# 7219_32_16.net
KiCad netlist of a schematic drawn in EAGLE
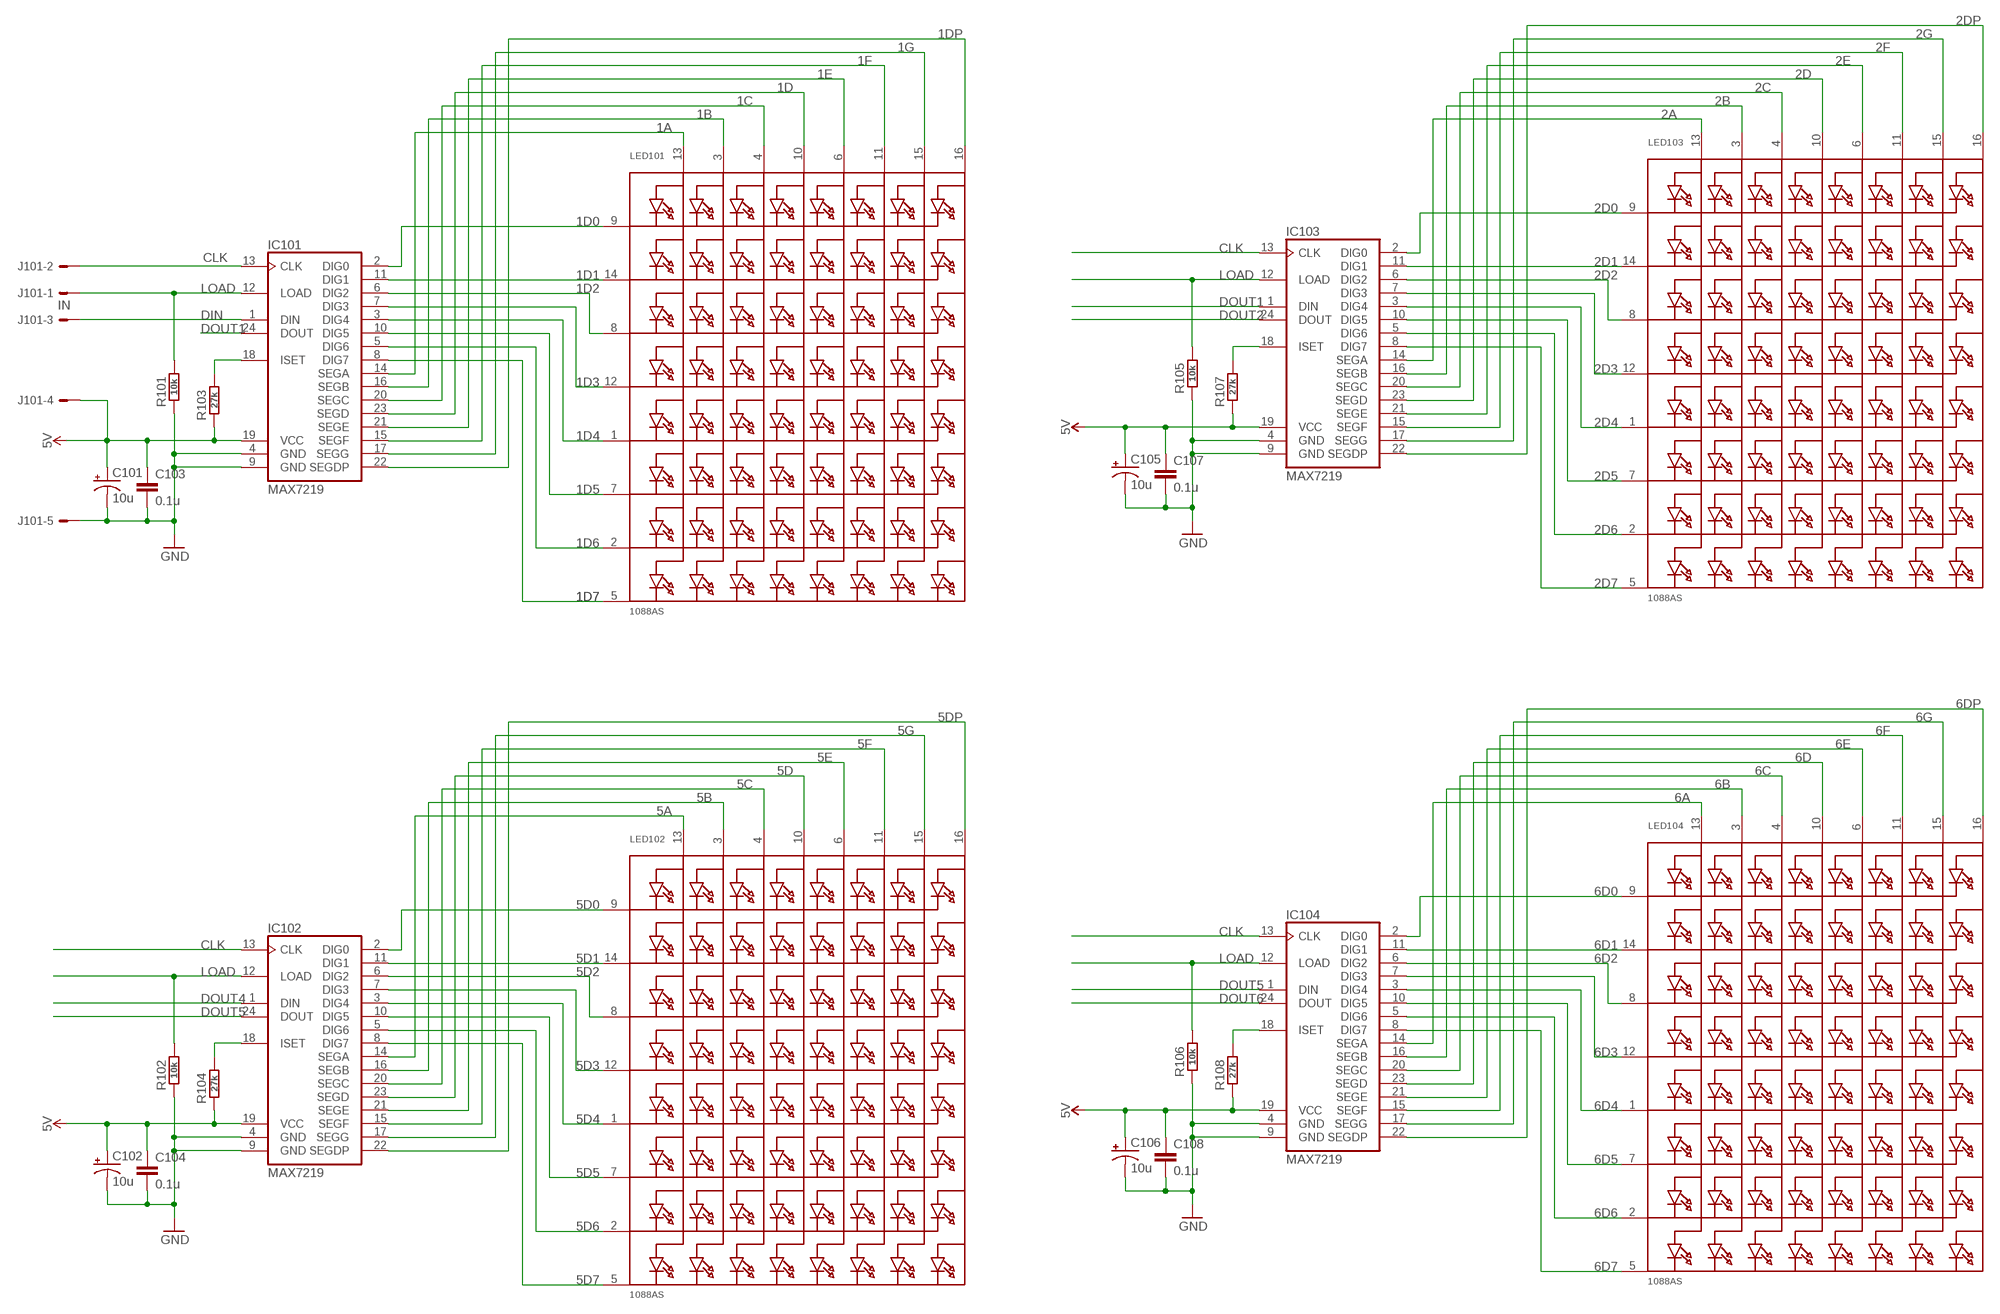
[diagram p0: schematic, sheet 1, part 1 of 2]
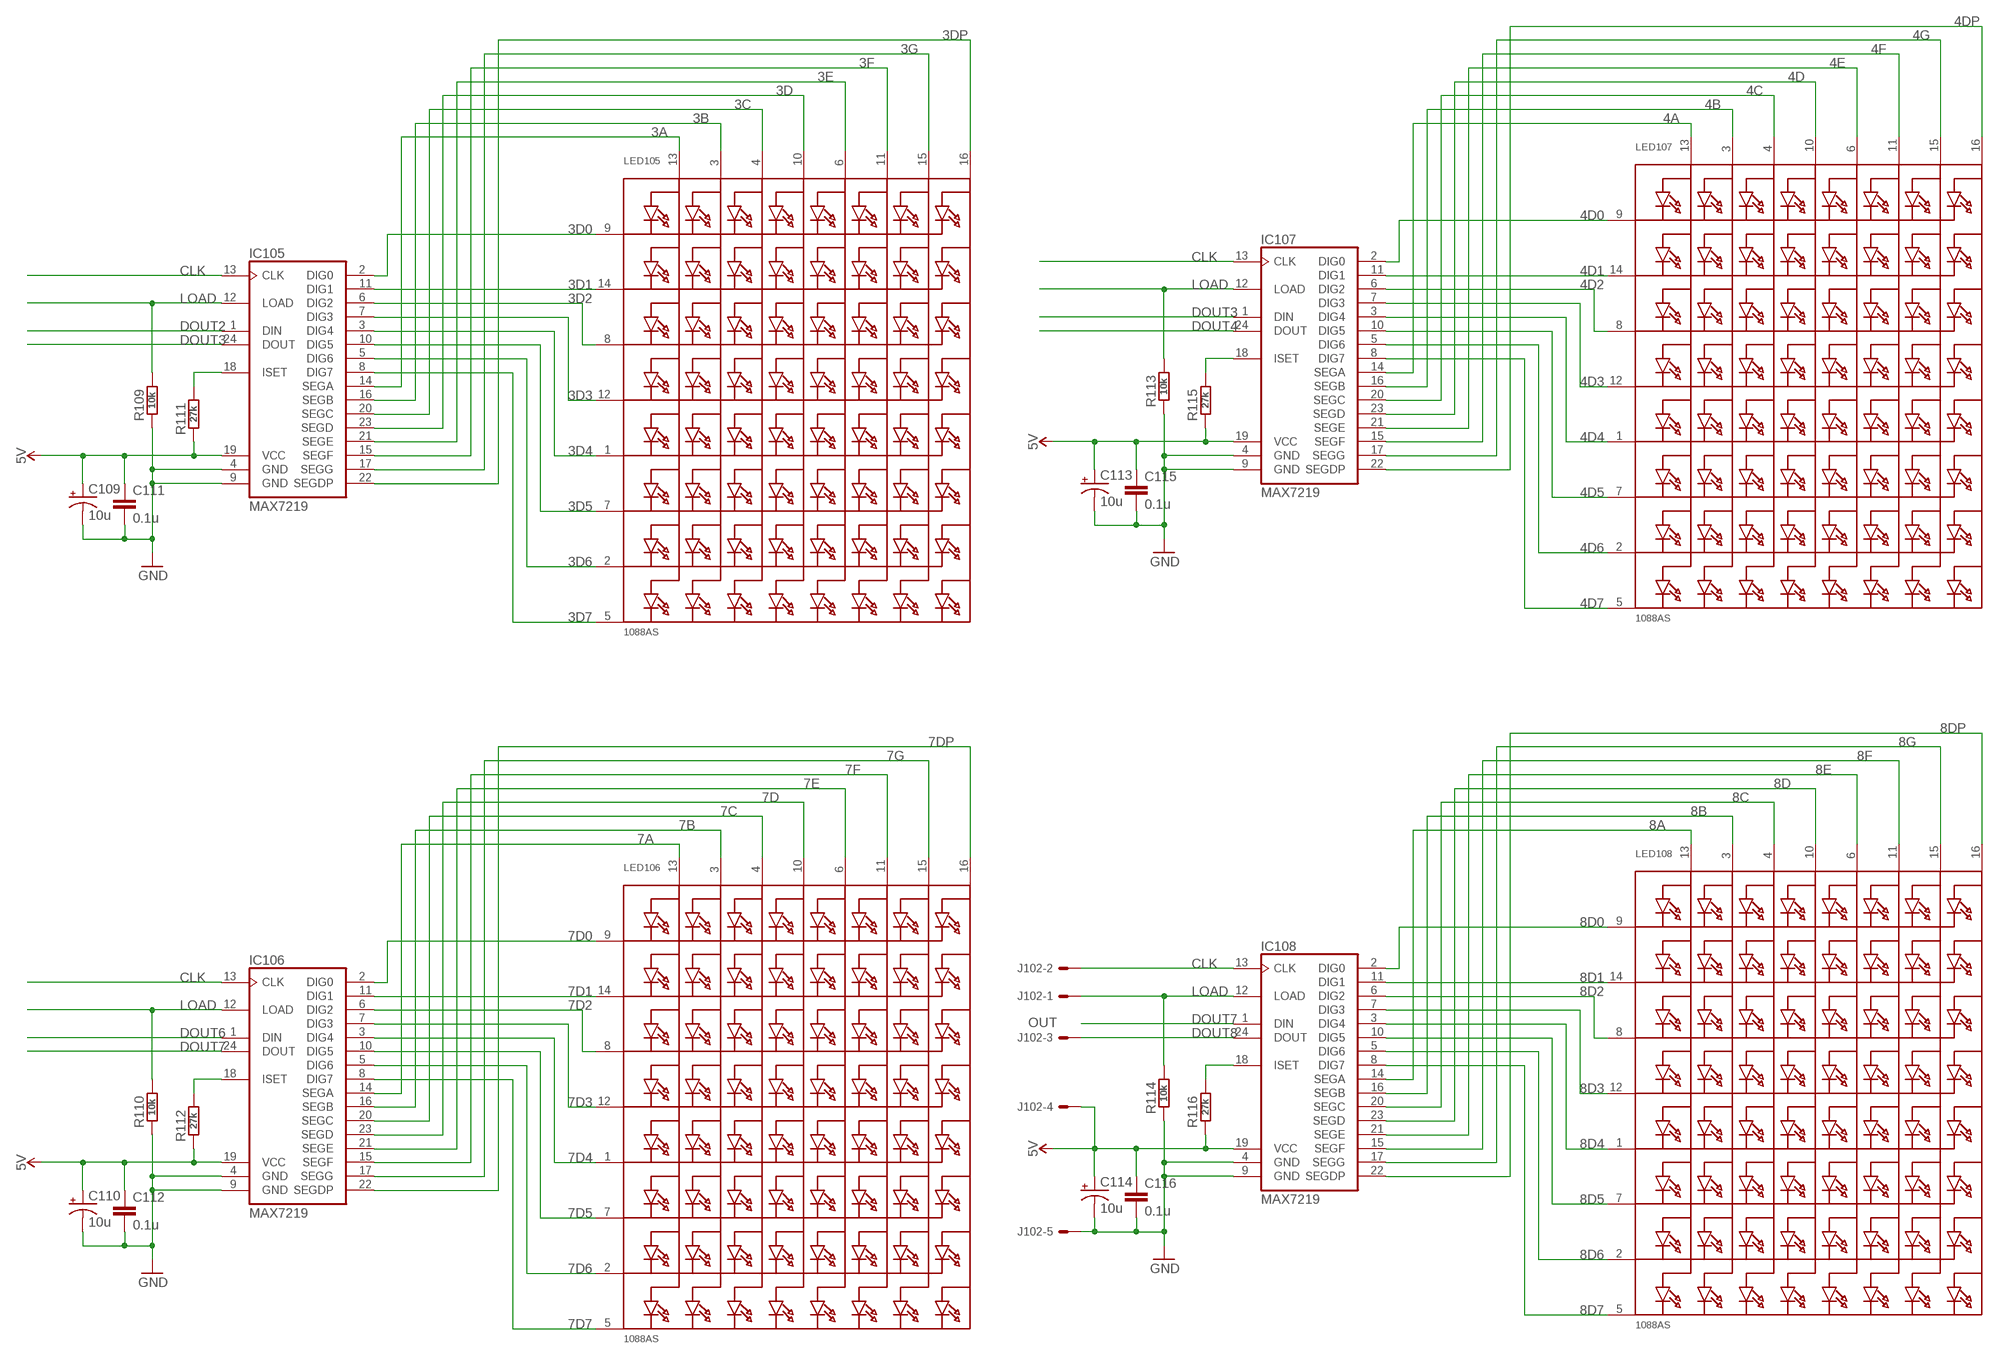
[diagram p1: schematic, sheet 1, part 2 of 2]
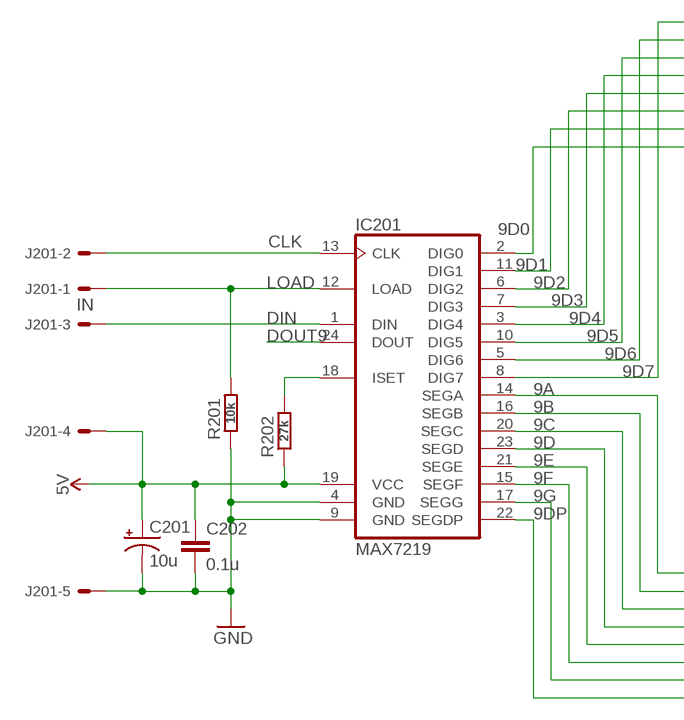
[diagram p2: schematic, sheet 2, part 1 of 2]
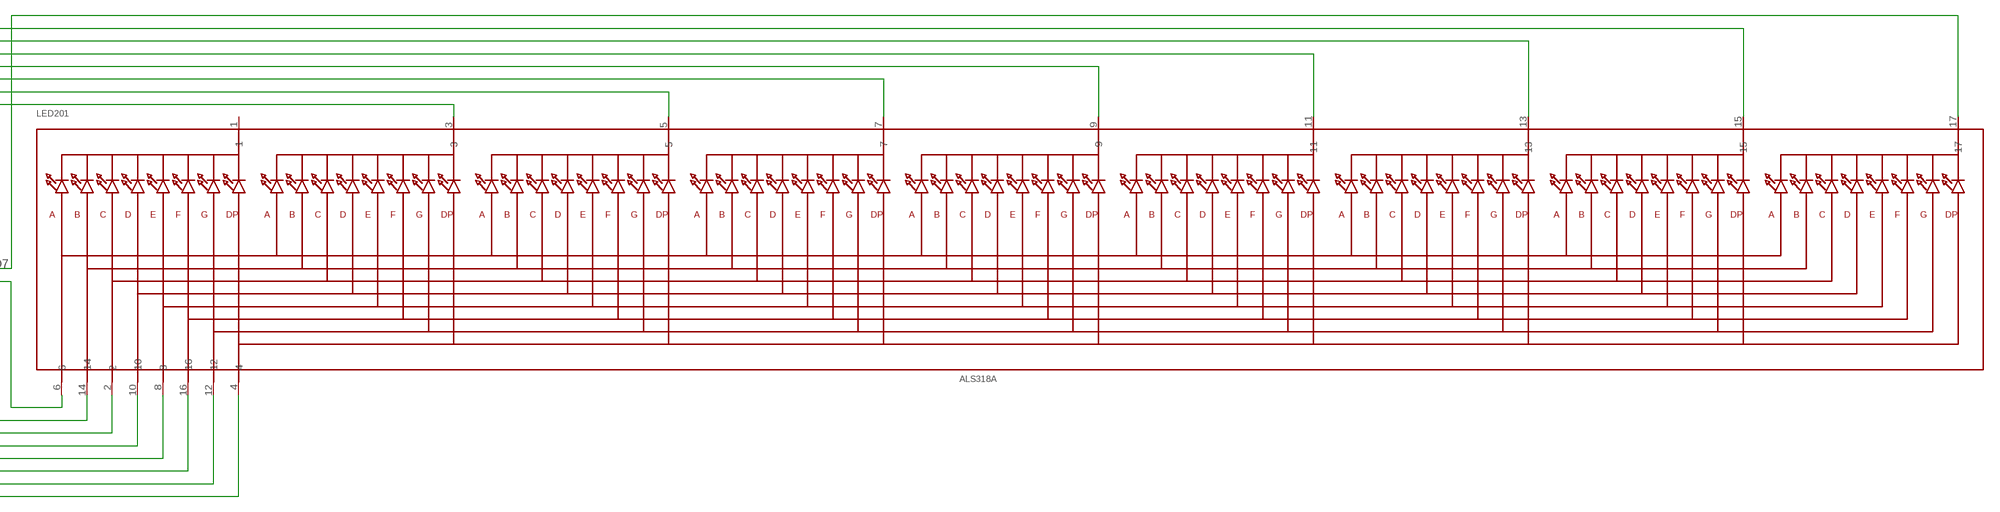
[diagram p3: schematic, sheet 2, part 2 of 2]
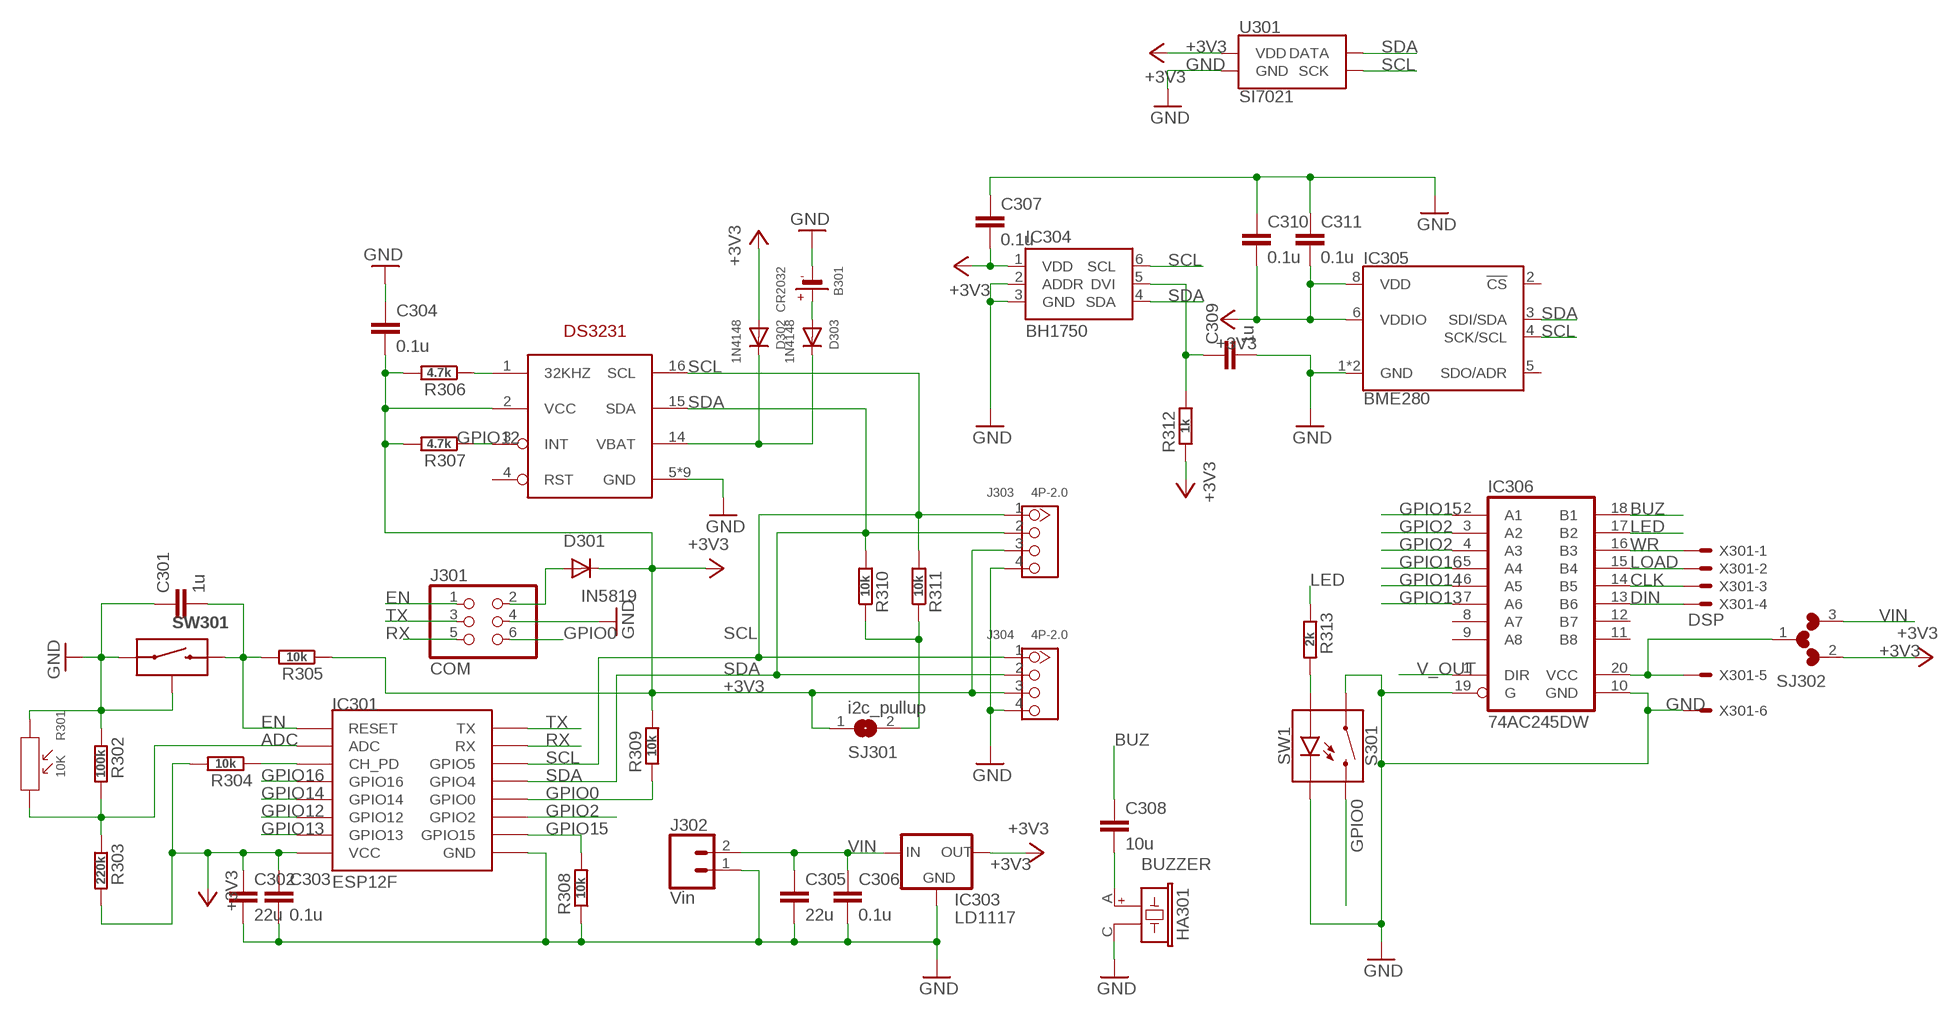
[diagram p4: schematic, sheet 3]
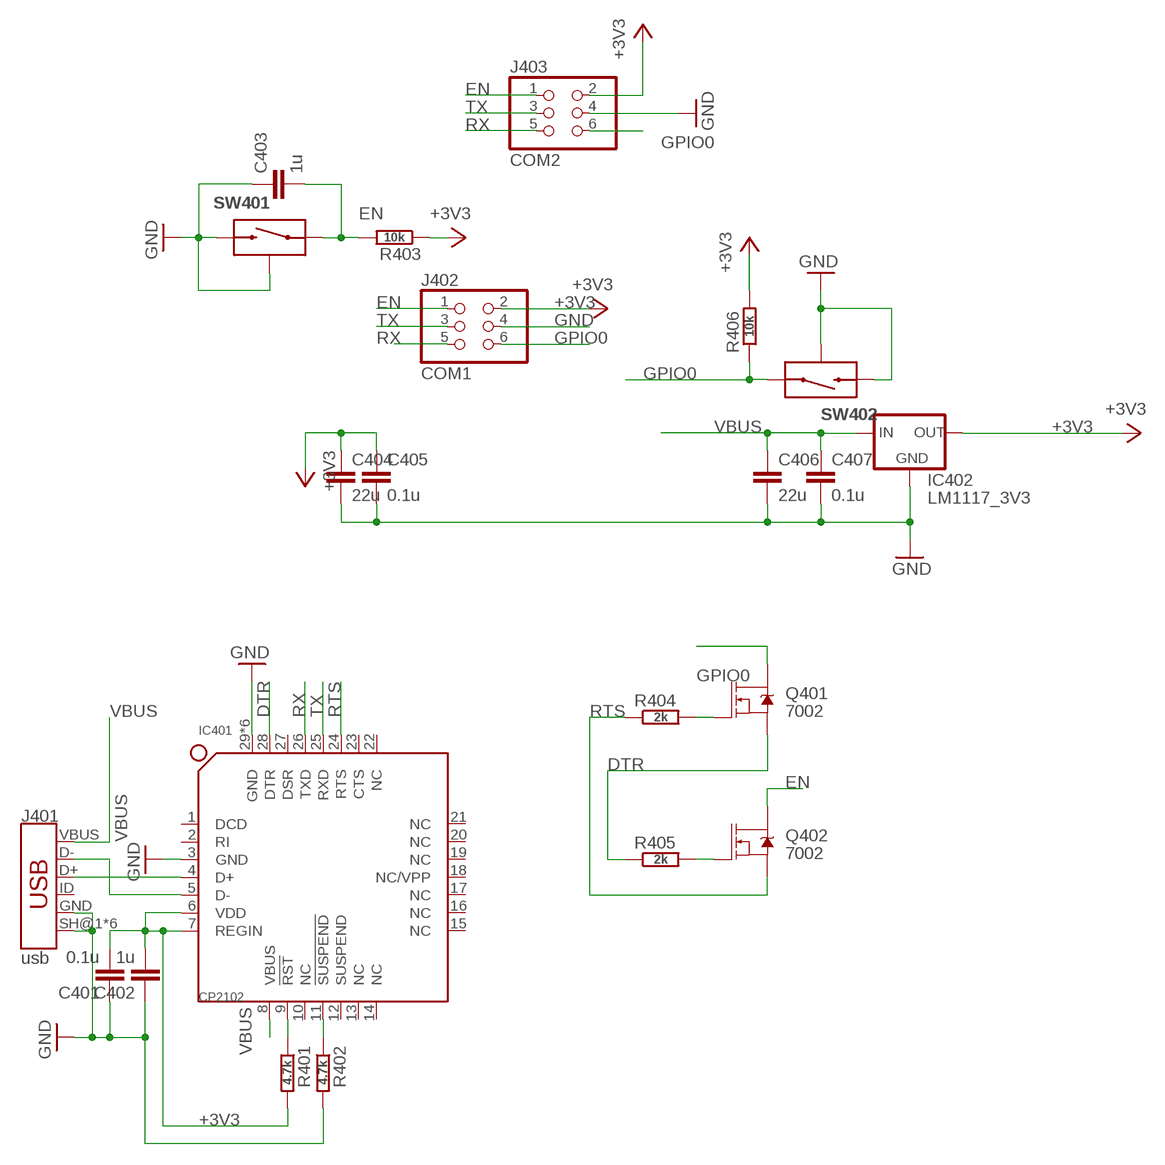
[diagram p5: schematic, sheet 4]

(export (version "E")
  (design (tool "Eeschema 10.0.6"))
  (components
    (comp (ref "B301")
      (value "CR2032")
      (footprint "eagle-import:CR2032")
      (libsource (lib "eagle-import") (part "BATTERYCR2032"))
    )
    (comp (ref "C301")
      (value "1u")
      (footprint "eagle-import:0603-CAP")
      (libsource (lib "eagle-import") (part "CAP0603-CAP"))
    )
    (comp (ref "C302")
      (value "22u")
      (footprint "eagle-import:0603-CAP")
      (libsource (lib "eagle-import") (part "CAP0603-CAP"))
    )
    (comp (ref "C303")
      (value "0.1u")
      (footprint "eagle-import:0603-CAP")
      (libsource (lib "eagle-import") (part "CAP0603-CAP"))
    )
    (comp (ref "C304")
      (value "0.1u")
      (footprint "eagle-import:0603-CAP")
      (libsource (lib "eagle-import") (part "CAP0603-CAP"))
    )
    (comp (ref "C305")
      (value "22u")
      (footprint "eagle-import:0603-CAP")
      (libsource (lib "eagle-import") (part "CAP0603-CAP"))
    )
    (comp (ref "C306")
      (value "0.1u")
      (footprint "eagle-import:0603-CAP")
      (libsource (lib "eagle-import") (part "CAP0603-CAP"))
    )
    (comp (ref "C307")
      (value "0.1u")
      (footprint "eagle-import:0603-CAP")
      (libsource (lib "eagle-import") (part "CAP0603-CAP"))
    )
    (comp (ref "C308")
      (value "10u")
      (footprint "eagle-import:0603-CAP")
      (libsource (lib "eagle-import") (part "CAP0603-CAP"))
    )
    (comp (ref "C309")
      (value "1u")
      (footprint "eagle-import:0603-CAP")
      (libsource (lib "eagle-import") (part "CAP0603-CAP"))
    )
    (comp (ref "C310")
      (value "0.1u")
      (footprint "eagle-import:0603-CAP")
      (libsource (lib "eagle-import") (part "CAP0603-CAP"))
    )
    (comp (ref "C311")
      (value "0.1u")
      (footprint "eagle-import:0603-CAP")
      (libsource (lib "eagle-import") (part "CAP0603-CAP"))
    )
    (comp (ref "D301")
      (value "IN5819")
      (footprint "eagle-import:SOD123")
      (libsource (lib "eagle-import") (part "DIODE-SOD123"))
    )
    (comp (ref "D302")
      (value "1N4148")
      (footprint "eagle-import:SOD-323F")
      (libsource (lib "eagle-import") (part "DIODESOD-323F"))
    )
    (comp (ref "D303")
      (value "1N4148")
      (footprint "eagle-import:SOD-323F")
      (libsource (lib "eagle-import") (part "DIODESOD-323F"))
    )
    (comp (ref "HA301")
      (value "BUZZER")
      (footprint "eagle-import:PBUZ_12X7.5")
      (libsource (lib "eagle-import") (part "PIEZO_BUZZERHYDZ12X7.5"))
    )
    (comp (ref "IC301")
      (value "ESP12F")
      (footprint "eagle-import:ESP12-SMD")
      (libsource (lib "eagle-import") (part "ESP12SMD"))
    )
    (comp (ref "IC302")
      (value "DS3231W")
      (footprint "eagle-import:SO16W")
      (libsource (lib "eagle-import") (part "DS3231W"))
    )
    (comp (ref "IC303")
      (value "LD1117")
      (footprint "eagle-import:SOT223")
      (libsource (lib "eagle-import") (part "V_REG_LD1117VXXSMD"))
    )
    (comp (ref "IC304")
      (value "BH1750")
      (footprint "eagle-import:WSOF6L")
      (libsource (lib "eagle-import") (part "BH1750"))
    )
    (comp (ref "IC305")
      (value "BME280")
      (footprint "eagle-import:LGA-8-2.5X2.5")
      (libsource (lib "eagle-import") (part "BME280"))
    )
    (comp (ref "IC306")
      (value "74AC245DW")
      (footprint "eagle-import:SO20W")
      (libsource (lib "eagle-import") (part "74245DWAC"))
    )
    (comp (ref "J301")
      (value "COM")
      (footprint "eagle-import:2X03_1.27MM_SMT")
      (libsource (lib "eagle-import") (part "HEADER-2X3SMT_1.27"))
    )
    (comp (ref "J302")
      (value "Vin")
      (footprint "eagle-import:1X02")
      (libsource (lib "eagle-import") (part "CONN_02"))
    )
    (comp (ref "J303")
      (value "4P-2.0")
      (footprint "eagle-import:HW4-2.0")
      (libsource (lib "eagle-import") (part "GROVE-CONNECTOR-DIP(4P-2.0)"))
    )
    (comp (ref "J304")
      (value "4P-2.0")
      (footprint "eagle-import:HW4-2.0")
      (libsource (lib "eagle-import") (part "GROVE-CONNECTOR-DIP(4P-2.0)"))
    )
    (comp (ref "R301")
      (value "10K")
      (footprint "eagle-import:SNR2-3.0")
      (fields (field (name "MPN") "PHOTORESISTOR-5528-10K"))
      (libsource (lib "eagle-import") (part "PHOTORESISTOR-5528-10K(2P-5.0X4.2MM)"))
    )
    (comp (ref "R302")
      (value "100k")
      (footprint "eagle-import:R0603")
      (libsource (lib "eagle-import") (part "R-EU_R0603"))
    )
    (comp (ref "R303")
      (value "220k")
      (footprint "eagle-import:R0603")
      (libsource (lib "eagle-import") (part "R-EU_R0603"))
    )
    (comp (ref "R304")
      (value "10k")
      (footprint "eagle-import:R0603")
      (libsource (lib "eagle-import") (part "R-EU_R0603"))
    )
    (comp (ref "R305")
      (value "10k")
      (footprint "eagle-import:R0603")
      (libsource (lib "eagle-import") (part "R-EU_R0603"))
    )
    (comp (ref "R306")
      (value "4.7k")
      (footprint "eagle-import:R0603")
      (libsource (lib "eagle-import") (part "R-EU_R0603"))
    )
    (comp (ref "R307")
      (value "4.7k")
      (footprint "eagle-import:R0603")
      (libsource (lib "eagle-import") (part "R-EU_R0603"))
    )
    (comp (ref "R308")
      (value "10k")
      (footprint "eagle-import:R0603")
      (libsource (lib "eagle-import") (part "R-EU_R0603"))
    )
    (comp (ref "R309")
      (value "10k")
      (footprint "eagle-import:R0603")
      (libsource (lib "eagle-import") (part "R-EU_R0603"))
    )
    (comp (ref "R310")
      (value "10k")
      (footprint "eagle-import:R0603")
      (libsource (lib "eagle-import") (part "R-EU_R0603"))
    )
    (comp (ref "R311")
      (value "10k")
      (footprint "eagle-import:R0603")
      (libsource (lib "eagle-import") (part "R-EU_R0603"))
    )
    (comp (ref "R312")
      (value "1k")
      (footprint "eagle-import:R0603")
      (libsource (lib "eagle-import") (part "R-EU_R0603"))
    )
    (comp (ref "R313")
      (value "2k")
      (footprint "eagle-import:R0603")
      (libsource (lib "eagle-import") (part "R-EU_R0603"))
    )
    (comp (ref "S301")
      (value "SW1")
      (footprint "eagle-import:TACTILE_SWITCH_LED_PTH_12MM_KIT")
      (libsource (lib "eagle-import") (part "MOMENTARY-SWITCH-SPST-LED-PTH-12MM-KIT"))
    )
    (comp (ref "SJ301")
      (value "i2c_pullup")
      (footprint "eagle-import:MICROBUILDER_SOLDERJUMPER_ARROW_NOPASTE")
      (libsource (lib "eagle-import") (part "MICROBUILDER_SOLDERJUMPER"))
    )
    (comp (ref "SJ302")
      (value "MICROBUILDER_SOLDERJUMPER3")
      (footprint "eagle-import:MICROBUILDER_SOLDERJUMPER_ARROW_NOPASTE_3")
      (libsource (lib "eagle-import") (part "MICROBUILDER_SOLDERJUMPER3"))
    )
    (comp (ref "SW301")
      (value "RST")
      (footprint "eagle-import:MICROPUSH-BUT_TOP")
      (libsource (lib "eagle-import") (part "MICROSWITCH-BUTTON"))
    )
    (comp (ref "U301")
      (value "SI7021")
      (footprint "eagle-import:DFN-6-3X3-SI7021")
      (libsource (lib "eagle-import") (part "SI7021"))
    )
    (comp (ref "X301")
      (value "DSP")
      (footprint "eagle-import:70543-06")
      (libsource (lib "eagle-import") (part "C-GRID-06-70543"))
    )
    (comp (ref "C201")
      (value "10u")
      (footprint "eagle-import:EIA3216")
      (libsource (lib "eagle-import") (part "CAP_POL1206"))
    )
    (comp (ref "C202")
      (value "0.1u")
      (footprint "eagle-import:0603-CAP")
      (libsource (lib "eagle-import") (part "CAP0603-CAP"))
    )
    (comp (ref "IC201")
      (value "MAX7219")
      (footprint "eagle-import:SO24L")
      (libsource (lib "eagle-import") (part "MAX7219CNGSO24"))
    )
    (comp (ref "J201")
      (value "IN")
      (footprint "eagle-import:70543-05")
      (libsource (lib "eagle-import") (part "C-GRID-05-70543"))
    )
    (comp (ref "LED201")
      (value "ALS318A")
      (footprint "eagle-import:АЛС318А")
      (libsource (lib "eagle-import") (part "АЛС318АBASE"))
    )
    (comp (ref "R201")
      (value "10k")
      (footprint "eagle-import:R0603")
      (libsource (lib "eagle-import") (part "R-EU_R0603"))
    )
    (comp (ref "R202")
      (value "27k")
      (footprint "eagle-import:R0603")
      (libsource (lib "eagle-import") (part "R-EU_R0603"))
    )
    (comp (ref "C401")
      (value "0.1u")
      (footprint "eagle-import:0603-CAP")
      (libsource (lib "eagle-import") (part "CAP0603-CAP"))
    )
    (comp (ref "C402")
      (value "1u")
      (footprint "eagle-import:0603-CAP")
      (libsource (lib "eagle-import") (part "CAP0603-CAP"))
    )
    (comp (ref "C403")
      (value "1u")
      (footprint "eagle-import:0603-CAP")
      (libsource (lib "eagle-import") (part "CAP0603-CAP"))
    )
    (comp (ref "C404")
      (value "22u")
      (footprint "eagle-import:0603-CAP")
      (libsource (lib "eagle-import") (part "CAP0603-CAP"))
    )
    (comp (ref "C405")
      (value "0.1u")
      (footprint "eagle-import:0603-CAP")
      (libsource (lib "eagle-import") (part "CAP0603-CAP"))
    )
    (comp (ref "C406")
      (value "22u")
      (footprint "eagle-import:0603-CAP")
      (libsource (lib "eagle-import") (part "CAP0603-CAP"))
    )
    (comp (ref "C407")
      (value "0.1u")
      (footprint "eagle-import:0603-CAP")
      (libsource (lib "eagle-import") (part "CAP0603-CAP"))
    )
    (comp (ref "IC401")
      (value "CP2102")
      (footprint "eagle-import:QFN28G_0.5-5X5MM")
      (fields (field (name "MPN") "CP2102-GMR"))
      (libsource (lib "eagle-import") (part "CP2102-GMR(QFN28)"))
    )
    (comp (ref "IC402")
      (value "LM1117_3V3")
      (footprint "eagle-import:SOT223")
      (libsource (lib "eagle-import") (part "V_REG_LD1117VXXSMD"))
    )
    (comp (ref "J401")
      (value "usb")
      (footprint "eagle-import:USB-B-MICRO-SMD_MY")
      (libsource (lib "eagle-import") (part "USB_MICRO-BFEMALE_SMT_"))
    )
    (comp (ref "J402")
      (value "COM1")
      (footprint "eagle-import:2X03_1.27MM_SMT")
      (libsource (lib "eagle-import") (part "HEADER-2X3SMT_1.27"))
    )
    (comp (ref "J403")
      (value "COM2")
      (footprint "eagle-import:2X03")
      (libsource (lib "eagle-import") (part "HEADER-2X3TH"))
    )
    (comp (ref "Q401")
      (value "7002")
      (footprint "eagle-import:SOT23-3")
      (libsource (lib "eagle-import") (part "MOSFET-NCH-2N7002"))
    )
    (comp (ref "Q402")
      (value "7002")
      (footprint "eagle-import:SOT23-3")
      (libsource (lib "eagle-import") (part "MOSFET-NCH-2N7002"))
    )
    (comp (ref "R401")
      (value "4.7k")
      (footprint "eagle-import:R0603")
      (libsource (lib "eagle-import") (part "R-EU_R0603"))
    )
    (comp (ref "R402")
      (value "4.7k")
      (footprint "eagle-import:R0603")
      (libsource (lib "eagle-import") (part "R-EU_R0603"))
    )
    (comp (ref "R403")
      (value "10k")
      (footprint "eagle-import:R0603")
      (libsource (lib "eagle-import") (part "R-EU_R0603"))
    )
    (comp (ref "R404")
      (value "2k")
      (footprint "eagle-import:R0603")
      (libsource (lib "eagle-import") (part "R-EU_R0603"))
    )
    (comp (ref "R405")
      (value "2k")
      (footprint "eagle-import:R0603")
      (libsource (lib "eagle-import") (part "R-EU_R0603"))
    )
    (comp (ref "R406")
      (value "10k")
      (footprint "eagle-import:R0603")
      (libsource (lib "eagle-import") (part "R-EU_R0603"))
    )
    (comp (ref "SW401")
      (value "RST")
      (footprint "eagle-import:MICROPUSH-BUT_TOP")
      (libsource (lib "eagle-import") (part "MICROSWITCH-BUTTON"))
    )
    (comp (ref "SW402")
      (value "PRG")
      (footprint "eagle-import:MICROPUSH-BUT_TOP")
      (libsource (lib "eagle-import") (part "MICROSWITCH-BUTTON"))
    )
    (comp (ref "C101")
      (value "10u")
      (footprint "eagle-import:EIA3216")
      (libsource (lib "eagle-import") (part "CAP_POL1206"))
    )
    (comp (ref "C102")
      (value "10u")
      (footprint "eagle-import:EIA3216")
      (libsource (lib "eagle-import") (part "CAP_POL1206"))
    )
    (comp (ref "C103")
      (value "0.1u")
      (footprint "eagle-import:0603-CAP")
      (libsource (lib "eagle-import") (part "CAP0603-CAP"))
    )
    (comp (ref "C104")
      (value "0.1u")
      (footprint "eagle-import:0603-CAP")
      (libsource (lib "eagle-import") (part "CAP0603-CAP"))
    )
    (comp (ref "C105")
      (value "10u")
      (footprint "eagle-import:EIA3216")
      (libsource (lib "eagle-import") (part "CAP_POL1206"))
    )
    (comp (ref "C106")
      (value "10u")
      (footprint "eagle-import:EIA3216")
      (libsource (lib "eagle-import") (part "CAP_POL1206"))
    )
    (comp (ref "C107")
      (value "0.1u")
      (footprint "eagle-import:0603-CAP")
      (libsource (lib "eagle-import") (part "CAP0603-CAP"))
    )
    (comp (ref "C108")
      (value "0.1u")
      (footprint "eagle-import:0603-CAP")
      (libsource (lib "eagle-import") (part "CAP0603-CAP"))
    )
    (comp (ref "C109")
      (value "10u")
      (footprint "eagle-import:EIA3216")
      (libsource (lib "eagle-import") (part "CAP_POL1206"))
    )
    (comp (ref "C110")
      (value "10u")
      (footprint "eagle-import:EIA3216")
      (libsource (lib "eagle-import") (part "CAP_POL1206"))
    )
    (comp (ref "C111")
      (value "0.1u")
      (footprint "eagle-import:0603-CAP")
      (libsource (lib "eagle-import") (part "CAP0603-CAP"))
    )
    (comp (ref "C112")
      (value "0.1u")
      (footprint "eagle-import:0603-CAP")
      (libsource (lib "eagle-import") (part "CAP0603-CAP"))
    )
    (comp (ref "C113")
      (value "10u")
      (footprint "eagle-import:EIA3216")
      (libsource (lib "eagle-import") (part "CAP_POL1206"))
    )
    (comp (ref "C114")
      (value "10u")
      (footprint "eagle-import:EIA3216")
      (libsource (lib "eagle-import") (part "CAP_POL1206"))
    )
    (comp (ref "C115")
      (value "0.1u")
      (footprint "eagle-import:0603-CAP")
      (libsource (lib "eagle-import") (part "CAP0603-CAP"))
    )
    (comp (ref "C116")
      (value "0.1u")
      (footprint "eagle-import:0603-CAP")
      (libsource (lib "eagle-import") (part "CAP0603-CAP"))
    )
    (comp (ref "IC101")
      (value "MAX7219")
      (footprint "eagle-import:SO24L")
      (libsource (lib "eagle-import") (part "MAX7219CNGSO24"))
    )
    (comp (ref "IC102")
      (value "MAX7219")
      (footprint "eagle-import:SO24L")
      (libsource (lib "eagle-import") (part "MAX7219CNGSO24"))
    )
    (comp (ref "IC103")
      (value "MAX7219")
      (footprint "eagle-import:SO24L")
      (libsource (lib "eagle-import") (part "MAX7219CNGSO24"))
    )
    (comp (ref "IC104")
      (value "MAX7219")
      (footprint "eagle-import:SO24L")
      (libsource (lib "eagle-import") (part "MAX7219CNGSO24"))
    )
    (comp (ref "IC105")
      (value "MAX7219")
      (footprint "eagle-import:SO24L")
      (libsource (lib "eagle-import") (part "MAX7219CNGSO24"))
    )
    (comp (ref "IC106")
      (value "MAX7219")
      (footprint "eagle-import:SO24L")
      (libsource (lib "eagle-import") (part "MAX7219CNGSO24"))
    )
    (comp (ref "IC107")
      (value "MAX7219")
      (footprint "eagle-import:SO24L")
      (libsource (lib "eagle-import") (part "MAX7219CNGSO24"))
    )
    (comp (ref "IC108")
      (value "MAX7219")
      (footprint "eagle-import:SO24L")
      (libsource (lib "eagle-import") (part "MAX7219CNGSO24"))
    )
    (comp (ref "J101")
      (value "IN")
      (footprint "eagle-import:70543-05")
      (libsource (lib "eagle-import") (part "C-GRID-05-70543"))
    )
    (comp (ref "J102")
      (value "OUT")
      (footprint "eagle-import:70543-05")
      (libsource (lib "eagle-import") (part "C-GRID-05-70543"))
    )
    (comp (ref "LED101")
      (value "1088AS")
      (footprint "eagle-import:SEGMENT_BL-M12A881UR")
      (libsource (lib "eagle-import") (part "DISP_SEGMENT_8X8_ROWCATHODEM12A881UR"))
    )
    (comp (ref "LED102")
      (value "1088AS")
      (footprint "eagle-import:SEGMENT_BL-M12A881UR")
      (libsource (lib "eagle-import") (part "DISP_SEGMENT_8X8_ROWCATHODEM12A881UR"))
    )
    (comp (ref "LED103")
      (value "1088AS")
      (footprint "eagle-import:SEGMENT_BL-M12A881UR")
      (libsource (lib "eagle-import") (part "DISP_SEGMENT_8X8_ROWCATHODEM12A881UR"))
    )
    (comp (ref "LED104")
      (value "1088AS")
      (footprint "eagle-import:SEGMENT_BL-M12A881UR")
      (libsource (lib "eagle-import") (part "DISP_SEGMENT_8X8_ROWCATHODEM12A881UR"))
    )
    (comp (ref "LED105")
      (value "1088AS")
      (footprint "eagle-import:SEGMENT_BL-M12A881UR")
      (libsource (lib "eagle-import") (part "DISP_SEGMENT_8X8_ROWCATHODEM12A881UR"))
    )
    (comp (ref "LED106")
      (value "1088AS")
      (footprint "eagle-import:SEGMENT_BL-M12A881UR")
      (libsource (lib "eagle-import") (part "DISP_SEGMENT_8X8_ROWCATHODEM12A881UR"))
    )
    (comp (ref "LED107")
      (value "1088AS")
      (footprint "eagle-import:SEGMENT_BL-M12A881UR")
      (libsource (lib "eagle-import") (part "DISP_SEGMENT_8X8_ROWCATHODEM12A881UR"))
    )
    (comp (ref "LED108")
      (value "1088AS")
      (footprint "eagle-import:SEGMENT_BL-M12A881UR")
      (libsource (lib "eagle-import") (part "DISP_SEGMENT_8X8_ROWCATHODEM12A881UR"))
    )
    (comp (ref "R101")
      (value "10k")
      (footprint "eagle-import:R0603")
      (libsource (lib "eagle-import") (part "R-EU_R0603"))
    )
    (comp (ref "R102")
      (value "10k")
      (footprint "eagle-import:R0603")
      (libsource (lib "eagle-import") (part "R-EU_R0603"))
    )
    (comp (ref "R103")
      (value "27k")
      (footprint "eagle-import:R0603")
      (libsource (lib "eagle-import") (part "R-EU_R0603"))
    )
    (comp (ref "R104")
      (value "27k")
      (footprint "eagle-import:R0603")
      (libsource (lib "eagle-import") (part "R-EU_R0603"))
    )
    (comp (ref "R105")
      (value "10k")
      (footprint "eagle-import:R0603")
      (libsource (lib "eagle-import") (part "R-EU_R0603"))
    )
    (comp (ref "R106")
      (value "10k")
      (footprint "eagle-import:R0603")
      (libsource (lib "eagle-import") (part "R-EU_R0603"))
    )
    (comp (ref "R107")
      (value "27k")
      (footprint "eagle-import:R0603")
      (libsource (lib "eagle-import") (part "R-EU_R0603"))
    )
    (comp (ref "R108")
      (value "27k")
      (footprint "eagle-import:R0603")
      (libsource (lib "eagle-import") (part "R-EU_R0603"))
    )
    (comp (ref "R109")
      (value "10k")
      (footprint "eagle-import:R0603")
      (libsource (lib "eagle-import") (part "R-EU_R0603"))
    )
    (comp (ref "R110")
      (value "10k")
      (footprint "eagle-import:R0603")
      (libsource (lib "eagle-import") (part "R-EU_R0603"))
    )
    (comp (ref "R111")
      (value "27k")
      (footprint "eagle-import:R0603")
      (libsource (lib "eagle-import") (part "R-EU_R0603"))
    )
    (comp (ref "R112")
      (value "27k")
      (footprint "eagle-import:R0603")
      (libsource (lib "eagle-import") (part "R-EU_R0603"))
    )
    (comp (ref "R113")
      (value "10k")
      (footprint "eagle-import:R0603")
      (libsource (lib "eagle-import") (part "R-EU_R0603"))
    )
    (comp (ref "R114")
      (value "10k")
      (footprint "eagle-import:R0603")
      (libsource (lib "eagle-import") (part "R-EU_R0603"))
    )
    (comp (ref "R115")
      (value "27k")
      (footprint "eagle-import:R0603")
      (libsource (lib "eagle-import") (part "R-EU_R0603"))
    )
    (comp (ref "R116")
      (value "27k")
      (footprint "eagle-import:R0603")
      (libsource (lib "eagle-import") (part "R-EU_R0603"))
    )
  )
  (nets
    (net (code "1") (name "+3V3") (class "Default")
      (node (ref "C302") (pin "1") (pinfunction "1_1") (pintype "passive"))
      (node (ref "C303") (pin "1") (pinfunction "1_1") (pintype "passive"))
      (node (ref "C304") (pin "2") (pinfunction "2_2") (pintype "passive"))
      (node (ref "C307") (pin "2") (pinfunction "2_2") (pintype "passive"))
      (node (ref "C310") (pin "2") (pinfunction "2_2") (pintype "passive"))
      (node (ref "C311") (pin "2") (pinfunction "2_2") (pintype "passive"))
      (node (ref "C401") (pin "2") (pinfunction "2_2") (pintype "passive"))
      (node (ref "C402") (pin "2") (pinfunction "2_2") (pintype "passive"))
      (node (ref "C404") (pin "1") (pinfunction "1_1") (pintype "passive"))
      (node (ref "C405") (pin "1") (pinfunction "1_1") (pintype "passive"))
      (node (ref "D301") (pin "C") (pinfunction "C_C") (pintype "passive"))
      (node (ref "D302") (pin "A") (pinfunction "A_A") (pintype "passive"))
      (node (ref "IC301") (pin "VCC") (pinfunction "VCC_VCC") (pintype "bidirectional"))
      (node (ref "IC302") (pin "2") (pinfunction "VCC_2") (pintype "input"))
      (node (ref "IC303") (pin "2") (pinfunction "OUT_2") (pintype "passive"))
      (node (ref "IC303") (pin "4") (pinfunction "OUT_4") (pintype "passive"))
      (node (ref "IC304") (pin "1") (pinfunction "VDD_1") (pintype "power_in"))
      (node (ref "IC305") (pin "6") (pinfunction "VDDIO_6") (pintype "bidirectional"))
      (node (ref "IC305") (pin "8") (pinfunction "VDD_8") (pintype "bidirectional"))
      (node (ref "IC401") (pin "6") (pinfunction "VDD_6") (pintype "bidirectional"))
      (node (ref "IC401") (pin "7") (pinfunction "REGIN_7") (pintype "bidirectional"))
      (node (ref "IC402") (pin "2") (pinfunction "OUT_2") (pintype "passive"))
      (node (ref "IC402") (pin "4") (pinfunction "OUT_4") (pintype "passive"))
      (node (ref "J303") (pin "3") (pinfunction "3_3") (pintype "bidirectional"))
      (node (ref "J304") (pin "3") (pinfunction "3_3") (pintype "bidirectional"))
      (node (ref "J402") (pin "2") (pinfunction "2_2") (pintype "passive"))
      (node (ref "J403") (pin "2") (pinfunction "2_2") (pintype "passive"))
      (node (ref "R303") (pin "2") (pinfunction "2_2") (pintype "passive"))
      (node (ref "R304") (pin "2") (pinfunction "2_2") (pintype "passive"))
      (node (ref "R305") (pin "1") (pinfunction "1_1") (pintype "passive"))
      (node (ref "R306") (pin "2") (pinfunction "2_2") (pintype "passive"))
      (node (ref "R307") (pin "2") (pinfunction "2_2") (pintype "passive"))
      (node (ref "R309") (pin "2") (pinfunction "2_2") (pintype "passive"))
      (node (ref "R312") (pin "1") (pinfunction "1_1") (pintype "passive"))
      (node (ref "R401") (pin "2") (pinfunction "2_2") (pintype "passive"))
      (node (ref "R403") (pin "1") (pinfunction "1_1") (pintype "passive"))
      (node (ref "R406") (pin "2") (pinfunction "2_2") (pintype "passive"))
      (node (ref "SJ301") (pin "1") (pinfunction "1_1") (pintype "passive"))
      (node (ref "SJ302") (pin "2") (pinfunction "2_2") (pintype "passive"))
      (node (ref "U301") (pin "VDD") (pinfunction "VDD_VDD") (pintype "power_in"))
    )
    (net (code "2") (name "+5V") (class "Default")
      (node (ref "C101") (pin "A") (pinfunction "+_A") (pintype "passive"))
      (node (ref "C102") (pin "A") (pinfunction "+_A") (pintype "passive"))
      (node (ref "C103") (pin "1") (pinfunction "1_1") (pintype "passive"))
      (node (ref "C104") (pin "1") (pinfunction "1_1") (pintype "passive"))
      (node (ref "C105") (pin "A") (pinfunction "+_A") (pintype "passive"))
      (node (ref "C106") (pin "A") (pinfunction "+_A") (pintype "passive"))
      (node (ref "C107") (pin "1") (pinfunction "1_1") (pintype "passive"))
      (node (ref "C108") (pin "1") (pinfunction "1_1") (pintype "passive"))
      (node (ref "C109") (pin "A") (pinfunction "+_A") (pintype "passive"))
      (node (ref "C110") (pin "A") (pinfunction "+_A") (pintype "passive"))
      (node (ref "C111") (pin "1") (pinfunction "1_1") (pintype "passive"))
      (node (ref "C112") (pin "1") (pinfunction "1_1") (pintype "passive"))
      (node (ref "C113") (pin "A") (pinfunction "+_A") (pintype "passive"))
      (node (ref "C114") (pin "A") (pinfunction "+_A") (pintype "passive"))
      (node (ref "C115") (pin "1") (pinfunction "1_1") (pintype "passive"))
      (node (ref "C116") (pin "1") (pinfunction "1_1") (pintype "passive"))
      (node (ref "C201") (pin "A") (pinfunction "+_A") (pintype "passive"))
      (node (ref "C202") (pin "1") (pinfunction "1_1") (pintype "passive"))
      (node (ref "IC101") (pin "19") (pinfunction "VCC_19") (pintype "power_in"))
      (node (ref "IC102") (pin "19") (pinfunction "VCC_19") (pintype "power_in"))
      (node (ref "IC103") (pin "19") (pinfunction "VCC_19") (pintype "power_in"))
      (node (ref "IC104") (pin "19") (pinfunction "VCC_19") (pintype "power_in"))
      (node (ref "IC105") (pin "19") (pinfunction "VCC_19") (pintype "power_in"))
      (node (ref "IC106") (pin "19") (pinfunction "VCC_19") (pintype "power_in"))
      (node (ref "IC107") (pin "19") (pinfunction "VCC_19") (pintype "power_in"))
      (node (ref "IC108") (pin "19") (pinfunction "VCC_19") (pintype "power_in"))
      (node (ref "IC201") (pin "19") (pinfunction "VCC_19") (pintype "power_in"))
      (node (ref "J101") (pin "4") (pinfunction "S_4") (pintype "passive"))
      (node (ref "J102") (pin "4") (pinfunction "S_4") (pintype "passive"))
      (node (ref "J201") (pin "4") (pinfunction "S_4") (pintype "passive"))
      (node (ref "R103") (pin "1") (pinfunction "1_1") (pintype "passive"))
      (node (ref "R104") (pin "1") (pinfunction "1_1") (pintype "passive"))
      (node (ref "R107") (pin "1") (pinfunction "1_1") (pintype "passive"))
      (node (ref "R108") (pin "1") (pinfunction "1_1") (pintype "passive"))
      (node (ref "R111") (pin "1") (pinfunction "1_1") (pintype "passive"))
      (node (ref "R112") (pin "1") (pinfunction "1_1") (pintype "passive"))
      (node (ref "R115") (pin "1") (pinfunction "1_1") (pintype "passive"))
      (node (ref "R116") (pin "1") (pinfunction "1_1") (pintype "passive"))
      (node (ref "R202") (pin "1") (pinfunction "1_1") (pintype "passive"))
    )
    (net (code "3") (name "1A") (class "Default")
      (node (ref "IC101") (pin "14") (pinfunction "SEGA_14") (pintype "output"))
      (node (ref "LED101") (pin "13") (pinfunction "A1_13") (pintype "bidirectional"))
    )
    (net (code "4") (name "1B") (class "Default")
      (node (ref "IC101") (pin "16") (pinfunction "SEGB_16") (pintype "output"))
      (node (ref "LED101") (pin "3") (pinfunction "A2_3") (pintype "bidirectional"))
    )
    (net (code "5") (name "1C") (class "Default")
      (node (ref "IC101") (pin "20") (pinfunction "SEGC_20") (pintype "output"))
      (node (ref "LED101") (pin "4") (pinfunction "A3_4") (pintype "bidirectional"))
    )
    (net (code "6") (name "1D") (class "Default")
      (node (ref "IC101") (pin "23") (pinfunction "SEGD_23") (pintype "output"))
      (node (ref "LED101") (pin "10") (pinfunction "A4_10") (pintype "bidirectional"))
    )
    (net (code "7") (name "1D0") (class "Default")
      (node (ref "IC101") (pin "2") (pinfunction "DIG0_2") (pintype "output"))
      (node (ref "LED101") (pin "9") (pinfunction "K1_9") (pintype "bidirectional"))
    )
    (net (code "8") (name "1D1") (class "Default")
      (node (ref "IC101") (pin "11") (pinfunction "DIG1_11") (pintype "output"))
      (node (ref "LED101") (pin "14") (pinfunction "K2_14") (pintype "bidirectional"))
    )
    (net (code "9") (name "1D2") (class "Default")
      (node (ref "IC101") (pin "6") (pinfunction "DIG2_6") (pintype "output"))
      (node (ref "LED101") (pin "8") (pinfunction "K3_8") (pintype "bidirectional"))
    )
    (net (code "10") (name "1D3") (class "Default")
      (node (ref "IC101") (pin "7") (pinfunction "DIG3_7") (pintype "output"))
      (node (ref "LED101") (pin "12") (pinfunction "K4_12") (pintype "bidirectional"))
    )
    (net (code "11") (name "1D4") (class "Default")
      (node (ref "IC101") (pin "3") (pinfunction "DIG4_3") (pintype "output"))
      (node (ref "LED101") (pin "1") (pinfunction "K5_1") (pintype "bidirectional"))
    )
    (net (code "12") (name "1D5") (class "Default")
      (node (ref "IC101") (pin "10") (pinfunction "DIG5_10") (pintype "output"))
      (node (ref "LED101") (pin "7") (pinfunction "K6_7") (pintype "bidirectional"))
    )
    (net (code "13") (name "1D6") (class "Default")
      (node (ref "IC101") (pin "5") (pinfunction "DIG6_5") (pintype "output"))
      (node (ref "LED101") (pin "2") (pinfunction "K7_2") (pintype "bidirectional"))
    )
    (net (code "14") (name "1D7") (class "Default")
      (node (ref "IC101") (pin "8") (pinfunction "DIG7_8") (pintype "output"))
      (node (ref "LED101") (pin "5") (pinfunction "K8_5") (pintype "bidirectional"))
    )
    (net (code "15") (name "1DP") (class "Default")
      (node (ref "IC101") (pin "22") (pinfunction "SEGDP_22") (pintype "output"))
      (node (ref "LED101") (pin "16") (pinfunction "A8_16") (pintype "bidirectional"))
    )
    (net (code "16") (name "1E") (class "Default")
      (node (ref "IC101") (pin "21") (pinfunction "SEGE_21") (pintype "output"))
      (node (ref "LED101") (pin "6") (pinfunction "A5_6") (pintype "bidirectional"))
    )
    (net (code "17") (name "1F") (class "Default")
      (node (ref "IC101") (pin "15") (pinfunction "SEGF_15") (pintype "output"))
      (node (ref "LED101") (pin "11") (pinfunction "A6_11") (pintype "bidirectional"))
    )
    (net (code "18") (name "1G") (class "Default")
      (node (ref "IC101") (pin "17") (pinfunction "SEGG_17") (pintype "output"))
      (node (ref "LED101") (pin "15") (pinfunction "A7_15") (pintype "bidirectional"))
    )
    (net (code "19") (name "2A") (class "Default")
      (node (ref "IC103") (pin "14") (pinfunction "SEGA_14") (pintype "output"))
      (node (ref "LED103") (pin "13") (pinfunction "A1_13") (pintype "bidirectional"))
    )
    (net (code "20") (name "2B") (class "Default")
      (node (ref "IC103") (pin "16") (pinfunction "SEGB_16") (pintype "output"))
      (node (ref "LED103") (pin "3") (pinfunction "A2_3") (pintype "bidirectional"))
    )
    (net (code "21") (name "2C") (class "Default")
      (node (ref "IC103") (pin "20") (pinfunction "SEGC_20") (pintype "output"))
      (node (ref "LED103") (pin "4") (pinfunction "A3_4") (pintype "bidirectional"))
    )
    (net (code "22") (name "2D") (class "Default")
      (node (ref "IC103") (pin "23") (pinfunction "SEGD_23") (pintype "output"))
      (node (ref "LED103") (pin "10") (pinfunction "A4_10") (pintype "bidirectional"))
    )
    (net (code "23") (name "2D0") (class "Default")
      (node (ref "IC103") (pin "2") (pinfunction "DIG0_2") (pintype "output"))
      (node (ref "LED103") (pin "9") (pinfunction "K1_9") (pintype "bidirectional"))
    )
    (net (code "24") (name "2D1") (class "Default")
      (node (ref "IC103") (pin "11") (pinfunction "DIG1_11") (pintype "output"))
      (node (ref "LED103") (pin "14") (pinfunction "K2_14") (pintype "bidirectional"))
    )
    (net (code "25") (name "2D2") (class "Default")
      (node (ref "IC103") (pin "6") (pinfunction "DIG2_6") (pintype "output"))
      (node (ref "LED103") (pin "8") (pinfunction "K3_8") (pintype "bidirectional"))
    )
    (net (code "26") (name "2D3") (class "Default")
      (node (ref "IC103") (pin "7") (pinfunction "DIG3_7") (pintype "output"))
      (node (ref "LED103") (pin "12") (pinfunction "K4_12") (pintype "bidirectional"))
    )
    (net (code "27") (name "2D4") (class "Default")
      (node (ref "IC103") (pin "3") (pinfunction "DIG4_3") (pintype "output"))
      (node (ref "LED103") (pin "1") (pinfunction "K5_1") (pintype "bidirectional"))
    )
    (net (code "28") (name "2D5") (class "Default")
      (node (ref "IC103") (pin "10") (pinfunction "DIG5_10") (pintype "output"))
      (node (ref "LED103") (pin "7") (pinfunction "K6_7") (pintype "bidirectional"))
    )
    (net (code "29") (name "2D6") (class "Default")
      (node (ref "IC103") (pin "5") (pinfunction "DIG6_5") (pintype "output"))
      (node (ref "LED103") (pin "2") (pinfunction "K7_2") (pintype "bidirectional"))
    )
    (net (code "30") (name "2D7") (class "Default")
      (node (ref "IC103") (pin "8") (pinfunction "DIG7_8") (pintype "output"))
      (node (ref "LED103") (pin "5") (pinfunction "K8_5") (pintype "bidirectional"))
    )
    (net (code "31") (name "2DP") (class "Default")
      (node (ref "IC103") (pin "22") (pinfunction "SEGDP_22") (pintype "output"))
      (node (ref "LED103") (pin "16") (pinfunction "A8_16") (pintype "bidirectional"))
    )
    (net (code "32") (name "2E") (class "Default")
      (node (ref "IC103") (pin "21") (pinfunction "SEGE_21") (pintype "output"))
      (node (ref "LED103") (pin "6") (pinfunction "A5_6") (pintype "bidirectional"))
    )
    (net (code "33") (name "2F") (class "Default")
      (node (ref "IC103") (pin "15") (pinfunction "SEGF_15") (pintype "output"))
      (node (ref "LED103") (pin "11") (pinfunction "A6_11") (pintype "bidirectional"))
    )
    (net (code "34") (name "2G") (class "Default")
      (node (ref "IC103") (pin "17") (pinfunction "SEGG_17") (pintype "output"))
      (node (ref "LED103") (pin "15") (pinfunction "A7_15") (pintype "bidirectional"))
    )
    (net (code "35") (name "3A") (class "Default")
      (node (ref "IC105") (pin "14") (pinfunction "SEGA_14") (pintype "output"))
      (node (ref "LED105") (pin "13") (pinfunction "A1_13") (pintype "bidirectional"))
    )
    (net (code "36") (name "3B") (class "Default")
      (node (ref "IC105") (pin "16") (pinfunction "SEGB_16") (pintype "output"))
      (node (ref "LED105") (pin "3") (pinfunction "A2_3") (pintype "bidirectional"))
    )
    (net (code "37") (name "3C") (class "Default")
      (node (ref "IC105") (pin "20") (pinfunction "SEGC_20") (pintype "output"))
      (node (ref "LED105") (pin "4") (pinfunction "A3_4") (pintype "bidirectional"))
    )
    (net (code "38") (name "3D") (class "Default")
      (node (ref "IC105") (pin "23") (pinfunction "SEGD_23") (pintype "output"))
      (node (ref "LED105") (pin "10") (pinfunction "A4_10") (pintype "bidirectional"))
    )
    (net (code "39") (name "3D0") (class "Default")
      (node (ref "IC105") (pin "2") (pinfunction "DIG0_2") (pintype "output"))
      (node (ref "LED105") (pin "9") (pinfunction "K1_9") (pintype "bidirectional"))
    )
    (net (code "40") (name "3D1") (class "Default")
      (node (ref "IC105") (pin "11") (pinfunction "DIG1_11") (pintype "output"))
      (node (ref "LED105") (pin "14") (pinfunction "K2_14") (pintype "bidirectional"))
    )
    (net (code "41") (name "3D2") (class "Default")
      (node (ref "IC105") (pin "6") (pinfunction "DIG2_6") (pintype "output"))
      (node (ref "LED105") (pin "8") (pinfunction "K3_8") (pintype "bidirectional"))
    )
    (net (code "42") (name "3D3") (class "Default")
      (node (ref "IC105") (pin "7") (pinfunction "DIG3_7") (pintype "output"))
      (node (ref "LED105") (pin "12") (pinfunction "K4_12") (pintype "bidirectional"))
    )
    (net (code "43") (name "3D4") (class "Default")
      (node (ref "IC105") (pin "3") (pinfunction "DIG4_3") (pintype "output"))
      (node (ref "LED105") (pin "1") (pinfunction "K5_1") (pintype "bidirectional"))
    )
    (net (code "44") (name "3D5") (class "Default")
      (node (ref "IC105") (pin "10") (pinfunction "DIG5_10") (pintype "output"))
      (node (ref "LED105") (pin "7") (pinfunction "K6_7") (pintype "bidirectional"))
    )
    (net (code "45") (name "3D6") (class "Default")
      (node (ref "IC105") (pin "5") (pinfunction "DIG6_5") (pintype "output"))
      (node (ref "LED105") (pin "2") (pinfunction "K7_2") (pintype "bidirectional"))
    )
    (net (code "46") (name "3D7") (class "Default")
      (node (ref "IC105") (pin "8") (pinfunction "DIG7_8") (pintype "output"))
      (node (ref "LED105") (pin "5") (pinfunction "K8_5") (pintype "bidirectional"))
    )
    (net (code "47") (name "3DP") (class "Default")
      (node (ref "IC105") (pin "22") (pinfunction "SEGDP_22") (pintype "output"))
      (node (ref "LED105") (pin "16") (pinfunction "A8_16") (pintype "bidirectional"))
    )
    (net (code "48") (name "3E") (class "Default")
      (node (ref "IC105") (pin "21") (pinfunction "SEGE_21") (pintype "output"))
      (node (ref "LED105") (pin "6") (pinfunction "A5_6") (pintype "bidirectional"))
    )
    (net (code "49") (name "3F") (class "Default")
      (node (ref "IC105") (pin "15") (pinfunction "SEGF_15") (pintype "output"))
      (node (ref "LED105") (pin "11") (pinfunction "A6_11") (pintype "bidirectional"))
    )
    (net (code "50") (name "3G") (class "Default")
      (node (ref "IC105") (pin "17") (pinfunction "SEGG_17") (pintype "output"))
      (node (ref "LED105") (pin "15") (pinfunction "A7_15") (pintype "bidirectional"))
    )
    (net (code "51") (name "4A") (class "Default")
      (node (ref "IC107") (pin "14") (pinfunction "SEGA_14") (pintype "output"))
      (node (ref "LED107") (pin "13") (pinfunction "A1_13") (pintype "bidirectional"))
    )
    (net (code "52") (name "4B") (class "Default")
      (node (ref "IC107") (pin "16") (pinfunction "SEGB_16") (pintype "output"))
      (node (ref "LED107") (pin "3") (pinfunction "A2_3") (pintype "bidirectional"))
    )
    (net (code "53") (name "4C") (class "Default")
      (node (ref "IC107") (pin "20") (pinfunction "SEGC_20") (pintype "output"))
      (node (ref "LED107") (pin "4") (pinfunction "A3_4") (pintype "bidirectional"))
    )
    (net (code "54") (name "4D") (class "Default")
      (node (ref "IC107") (pin "23") (pinfunction "SEGD_23") (pintype "output"))
      (node (ref "LED107") (pin "10") (pinfunction "A4_10") (pintype "bidirectional"))
    )
    (net (code "55") (name "4D0") (class "Default")
      (node (ref "IC107") (pin "2") (pinfunction "DIG0_2") (pintype "output"))
      (node (ref "LED107") (pin "9") (pinfunction "K1_9") (pintype "bidirectional"))
    )
    (net (code "56") (name "4D1") (class "Default")
      (node (ref "IC107") (pin "11") (pinfunction "DIG1_11") (pintype "output"))
      (node (ref "LED107") (pin "14") (pinfunction "K2_14") (pintype "bidirectional"))
    )
    (net (code "57") (name "4D2") (class "Default")
      (node (ref "IC107") (pin "6") (pinfunction "DIG2_6") (pintype "output"))
      (node (ref "LED107") (pin "8") (pinfunction "K3_8") (pintype "bidirectional"))
    )
    (net (code "58") (name "4D3") (class "Default")
      (node (ref "IC107") (pin "7") (pinfunction "DIG3_7") (pintype "output"))
      (node (ref "LED107") (pin "12") (pinfunction "K4_12") (pintype "bidirectional"))
    )
    (net (code "59") (name "4D4") (class "Default")
      (node (ref "IC107") (pin "3") (pinfunction "DIG4_3") (pintype "output"))
      (node (ref "LED107") (pin "1") (pinfunction "K5_1") (pintype "bidirectional"))
    )
    (net (code "60") (name "4D5") (class "Default")
      (node (ref "IC107") (pin "10") (pinfunction "DIG5_10") (pintype "output"))
      (node (ref "LED107") (pin "7") (pinfunction "K6_7") (pintype "bidirectional"))
    )
    (net (code "61") (name "4D6") (class "Default")
      (node (ref "IC107") (pin "5") (pinfunction "DIG6_5") (pintype "output"))
      (node (ref "LED107") (pin "2") (pinfunction "K7_2") (pintype "bidirectional"))
    )
    (net (code "62") (name "4D7") (class "Default")
      (node (ref "IC107") (pin "8") (pinfunction "DIG7_8") (pintype "output"))
      (node (ref "LED107") (pin "5") (pinfunction "K8_5") (pintype "bidirectional"))
    )
    (net (code "63") (name "4DP") (class "Default")
      (node (ref "IC107") (pin "22") (pinfunction "SEGDP_22") (pintype "output"))
      (node (ref "LED107") (pin "16") (pinfunction "A8_16") (pintype "bidirectional"))
    )
    (net (code "64") (name "4E") (class "Default")
      (node (ref "IC107") (pin "21") (pinfunction "SEGE_21") (pintype "output"))
      (node (ref "LED107") (pin "6") (pinfunction "A5_6") (pintype "bidirectional"))
    )
    (net (code "65") (name "4F") (class "Default")
      (node (ref "IC107") (pin "15") (pinfunction "SEGF_15") (pintype "output"))
      (node (ref "LED107") (pin "11") (pinfunction "A6_11") (pintype "bidirectional"))
    )
    (net (code "66") (name "4G") (class "Default")
      (node (ref "IC107") (pin "17") (pinfunction "SEGG_17") (pintype "output"))
      (node (ref "LED107") (pin "15") (pinfunction "A7_15") (pintype "bidirectional"))
    )
    (net (code "67") (name "5A") (class "Default")
      (node (ref "IC102") (pin "14") (pinfunction "SEGA_14") (pintype "output"))
      (node (ref "LED102") (pin "13") (pinfunction "A1_13") (pintype "bidirectional"))
    )
    (net (code "68") (name "5B") (class "Default")
      (node (ref "IC102") (pin "16") (pinfunction "SEGB_16") (pintype "output"))
      (node (ref "LED102") (pin "3") (pinfunction "A2_3") (pintype "bidirectional"))
    )
    (net (code "69") (name "5C") (class "Default")
      (node (ref "IC102") (pin "20") (pinfunction "SEGC_20") (pintype "output"))
      (node (ref "LED102") (pin "4") (pinfunction "A3_4") (pintype "bidirectional"))
    )
    (net (code "70") (name "5D") (class "Default")
      (node (ref "IC102") (pin "23") (pinfunction "SEGD_23") (pintype "output"))
      (node (ref "LED102") (pin "10") (pinfunction "A4_10") (pintype "bidirectional"))
    )
    (net (code "71") (name "5D0") (class "Default")
      (node (ref "IC102") (pin "2") (pinfunction "DIG0_2") (pintype "output"))
      (node (ref "LED102") (pin "9") (pinfunction "K1_9") (pintype "bidirectional"))
    )
    (net (code "72") (name "5D1") (class "Default")
      (node (ref "IC102") (pin "11") (pinfunction "DIG1_11") (pintype "output"))
      (node (ref "LED102") (pin "14") (pinfunction "K2_14") (pintype "bidirectional"))
    )
    (net (code "73") (name "5D2") (class "Default")
      (node (ref "IC102") (pin "6") (pinfunction "DIG2_6") (pintype "output"))
      (node (ref "LED102") (pin "8") (pinfunction "K3_8") (pintype "bidirectional"))
    )
    (net (code "74") (name "5D3") (class "Default")
      (node (ref "IC102") (pin "7") (pinfunction "DIG3_7") (pintype "output"))
      (node (ref "LED102") (pin "12") (pinfunction "K4_12") (pintype "bidirectional"))
    )
    (net (code "75") (name "5D4") (class "Default")
      (node (ref "IC102") (pin "3") (pinfunction "DIG4_3") (pintype "output"))
      (node (ref "LED102") (pin "1") (pinfunction "K5_1") (pintype "bidirectional"))
    )
    (net (code "76") (name "5D5") (class "Default")
      (node (ref "IC102") (pin "10") (pinfunction "DIG5_10") (pintype "output"))
      (node (ref "LED102") (pin "7") (pinfunction "K6_7") (pintype "bidirectional"))
    )
    (net (code "77") (name "5D6") (class "Default")
      (node (ref "IC102") (pin "5") (pinfunction "DIG6_5") (pintype "output"))
      (node (ref "LED102") (pin "2") (pinfunction "K7_2") (pintype "bidirectional"))
    )
    (net (code "78") (name "5D7") (class "Default")
      (node (ref "IC102") (pin "8") (pinfunction "DIG7_8") (pintype "output"))
      (node (ref "LED102") (pin "5") (pinfunction "K8_5") (pintype "bidirectional"))
    )
    (net (code "79") (name "5DP") (class "Default")
      (node (ref "IC102") (pin "22") (pinfunction "SEGDP_22") (pintype "output"))
      (node (ref "LED102") (pin "16") (pinfunction "A8_16") (pintype "bidirectional"))
    )
    (net (code "80") (name "5E") (class "Default")
      (node (ref "IC102") (pin "21") (pinfunction "SEGE_21") (pintype "output"))
      (node (ref "LED102") (pin "6") (pinfunction "A5_6") (pintype "bidirectional"))
    )
    (net (code "81") (name "5F") (class "Default")
      (node (ref "IC102") (pin "15") (pinfunction "SEGF_15") (pintype "output"))
      (node (ref "LED102") (pin "11") (pinfunction "A6_11") (pintype "bidirectional"))
    )
    (net (code "82") (name "5G") (class "Default")
      (node (ref "IC102") (pin "17") (pinfunction "SEGG_17") (pintype "output"))
      (node (ref "LED102") (pin "15") (pinfunction "A7_15") (pintype "bidirectional"))
    )
    (net (code "83") (name "6A") (class "Default")
      (node (ref "IC104") (pin "14") (pinfunction "SEGA_14") (pintype "output"))
      (node (ref "LED104") (pin "13") (pinfunction "A1_13") (pintype "bidirectional"))
    )
    (net (code "84") (name "6B") (class "Default")
      (node (ref "IC104") (pin "16") (pinfunction "SEGB_16") (pintype "output"))
      (node (ref "LED104") (pin "3") (pinfunction "A2_3") (pintype "bidirectional"))
    )
    (net (code "85") (name "6C") (class "Default")
      (node (ref "IC104") (pin "20") (pinfunction "SEGC_20") (pintype "output"))
      (node (ref "LED104") (pin "4") (pinfunction "A3_4") (pintype "bidirectional"))
    )
    (net (code "86") (name "6D") (class "Default")
      (node (ref "IC104") (pin "23") (pinfunction "SEGD_23") (pintype "output"))
      (node (ref "LED104") (pin "10") (pinfunction "A4_10") (pintype "bidirectional"))
    )
    (net (code "87") (name "6D0") (class "Default")
      (node (ref "IC104") (pin "2") (pinfunction "DIG0_2") (pintype "output"))
      (node (ref "LED104") (pin "9") (pinfunction "K1_9") (pintype "bidirectional"))
    )
    (net (code "88") (name "6D1") (class "Default")
      (node (ref "IC104") (pin "11") (pinfunction "DIG1_11") (pintype "output"))
      (node (ref "LED104") (pin "14") (pinfunction "K2_14") (pintype "bidirectional"))
    )
    (net (code "89") (name "6D2") (class "Default")
      (node (ref "IC104") (pin "6") (pinfunction "DIG2_6") (pintype "output"))
      (node (ref "LED104") (pin "8") (pinfunction "K3_8") (pintype "bidirectional"))
    )
    (net (code "90") (name "6D3") (class "Default")
      (node (ref "IC104") (pin "7") (pinfunction "DIG3_7") (pintype "output"))
      (node (ref "LED104") (pin "12") (pinfunction "K4_12") (pintype "bidirectional"))
    )
    (net (code "91") (name "6D4") (class "Default")
      (node (ref "IC104") (pin "3") (pinfunction "DIG4_3") (pintype "output"))
      (node (ref "LED104") (pin "1") (pinfunction "K5_1") (pintype "bidirectional"))
    )
    (net (code "92") (name "6D5") (class "Default")
      (node (ref "IC104") (pin "10") (pinfunction "DIG5_10") (pintype "output"))
      (node (ref "LED104") (pin "7") (pinfunction "K6_7") (pintype "bidirectional"))
    )
    (net (code "93") (name "6D6") (class "Default")
      (node (ref "IC104") (pin "5") (pinfunction "DIG6_5") (pintype "output"))
      (node (ref "LED104") (pin "2") (pinfunction "K7_2") (pintype "bidirectional"))
    )
    (net (code "94") (name "6D7") (class "Default")
      (node (ref "IC104") (pin "8") (pinfunction "DIG7_8") (pintype "output"))
      (node (ref "LED104") (pin "5") (pinfunction "K8_5") (pintype "bidirectional"))
    )
    (net (code "95") (name "6DP") (class "Default")
      (node (ref "IC104") (pin "22") (pinfunction "SEGDP_22") (pintype "output"))
      (node (ref "LED104") (pin "16") (pinfunction "A8_16") (pintype "bidirectional"))
    )
    (net (code "96") (name "6E") (class "Default")
      (node (ref "IC104") (pin "21") (pinfunction "SEGE_21") (pintype "output"))
      (node (ref "LED104") (pin "6") (pinfunction "A5_6") (pintype "bidirectional"))
    )
    (net (code "97") (name "6F") (class "Default")
      (node (ref "IC104") (pin "15") (pinfunction "SEGF_15") (pintype "output"))
      (node (ref "LED104") (pin "11") (pinfunction "A6_11") (pintype "bidirectional"))
    )
    (net (code "98") (name "6G") (class "Default")
      (node (ref "IC104") (pin "17") (pinfunction "SEGG_17") (pintype "output"))
      (node (ref "LED104") (pin "15") (pinfunction "A7_15") (pintype "bidirectional"))
    )
    (net (code "99") (name "7A") (class "Default")
      (node (ref "IC106") (pin "14") (pinfunction "SEGA_14") (pintype "output"))
      (node (ref "LED106") (pin "13") (pinfunction "A1_13") (pintype "bidirectional"))
    )
    (net (code "100") (name "7B") (class "Default")
      (node (ref "IC106") (pin "16") (pinfunction "SEGB_16") (pintype "output"))
      (node (ref "LED106") (pin "3") (pinfunction "A2_3") (pintype "bidirectional"))
    )
    (net (code "101") (name "7C") (class "Default")
      (node (ref "IC106") (pin "20") (pinfunction "SEGC_20") (pintype "output"))
      (node (ref "LED106") (pin "4") (pinfunction "A3_4") (pintype "bidirectional"))
    )
    (net (code "102") (name "7D") (class "Default")
      (node (ref "IC106") (pin "23") (pinfunction "SEGD_23") (pintype "output"))
      (node (ref "LED106") (pin "10") (pinfunction "A4_10") (pintype "bidirectional"))
    )
    (net (code "103") (name "7D0") (class "Default")
      (node (ref "IC106") (pin "2") (pinfunction "DIG0_2") (pintype "output"))
      (node (ref "LED106") (pin "9") (pinfunction "K1_9") (pintype "bidirectional"))
    )
    (net (code "104") (name "7D1") (class "Default")
      (node (ref "IC106") (pin "11") (pinfunction "DIG1_11") (pintype "output"))
      (node (ref "LED106") (pin "14") (pinfunction "K2_14") (pintype "bidirectional"))
    )
    (net (code "105") (name "7D2") (class "Default")
      (node (ref "IC106") (pin "6") (pinfunction "DIG2_6") (pintype "output"))
      (node (ref "LED106") (pin "8") (pinfunction "K3_8") (pintype "bidirectional"))
    )
    (net (code "106") (name "7D3") (class "Default")
      (node (ref "IC106") (pin "7") (pinfunction "DIG3_7") (pintype "output"))
      (node (ref "LED106") (pin "12") (pinfunction "K4_12") (pintype "bidirectional"))
    )
    (net (code "107") (name "7D4") (class "Default")
      (node (ref "IC106") (pin "3") (pinfunction "DIG4_3") (pintype "output"))
      (node (ref "LED106") (pin "1") (pinfunction "K5_1") (pintype "bidirectional"))
    )
    (net (code "108") (name "7D5") (class "Default")
      (node (ref "IC106") (pin "10") (pinfunction "DIG5_10") (pintype "output"))
      (node (ref "LED106") (pin "7") (pinfunction "K6_7") (pintype "bidirectional"))
    )
    (net (code "109") (name "7D6") (class "Default")
      (node (ref "IC106") (pin "5") (pinfunction "DIG6_5") (pintype "output"))
      (node (ref "LED106") (pin "2") (pinfunction "K7_2") (pintype "bidirectional"))
    )
    (net (code "110") (name "7D7") (class "Default")
      (node (ref "IC106") (pin "8") (pinfunction "DIG7_8") (pintype "output"))
      (node (ref "LED106") (pin "5") (pinfunction "K8_5") (pintype "bidirectional"))
    )
    (net (code "111") (name "7DP") (class "Default")
      (node (ref "IC106") (pin "22") (pinfunction "SEGDP_22") (pintype "output"))
      (node (ref "LED106") (pin "16") (pinfunction "A8_16") (pintype "bidirectional"))
    )
    (net (code "112") (name "7E") (class "Default")
      (node (ref "IC106") (pin "21") (pinfunction "SEGE_21") (pintype "output"))
      (node (ref "LED106") (pin "6") (pinfunction "A5_6") (pintype "bidirectional"))
    )
    (net (code "113") (name "7F") (class "Default")
      (node (ref "IC106") (pin "15") (pinfunction "SEGF_15") (pintype "output"))
      (node (ref "LED106") (pin "11") (pinfunction "A6_11") (pintype "bidirectional"))
    )
    (net (code "114") (name "7G") (class "Default")
      (node (ref "IC106") (pin "17") (pinfunction "SEGG_17") (pintype "output"))
      (node (ref "LED106") (pin "15") (pinfunction "A7_15") (pintype "bidirectional"))
    )
    (net (code "115") (name "8A") (class "Default")
      (node (ref "IC108") (pin "14") (pinfunction "SEGA_14") (pintype "output"))
      (node (ref "LED108") (pin "13") (pinfunction "A1_13") (pintype "bidirectional"))
    )
    (net (code "116") (name "8B") (class "Default")
      (node (ref "IC108") (pin "16") (pinfunction "SEGB_16") (pintype "output"))
      (node (ref "LED108") (pin "3") (pinfunction "A2_3") (pintype "bidirectional"))
    )
    (net (code "117") (name "8C") (class "Default")
      (node (ref "IC108") (pin "20") (pinfunction "SEGC_20") (pintype "output"))
      (node (ref "LED108") (pin "4") (pinfunction "A3_4") (pintype "bidirectional"))
    )
    (net (code "118") (name "8D") (class "Default")
      (node (ref "IC108") (pin "23") (pinfunction "SEGD_23") (pintype "output"))
      (node (ref "LED108") (pin "10") (pinfunction "A4_10") (pintype "bidirectional"))
    )
    (net (code "119") (name "8D0") (class "Default")
      (node (ref "IC108") (pin "2") (pinfunction "DIG0_2") (pintype "output"))
      (node (ref "LED108") (pin "9") (pinfunction "K1_9") (pintype "bidirectional"))
    )
    (net (code "120") (name "8D1") (class "Default")
      (node (ref "IC108") (pin "11") (pinfunction "DIG1_11") (pintype "output"))
      (node (ref "LED108") (pin "14") (pinfunction "K2_14") (pintype "bidirectional"))
    )
    (net (code "121") (name "8D2") (class "Default")
      (node (ref "IC108") (pin "6") (pinfunction "DIG2_6") (pintype "output"))
      (node (ref "LED108") (pin "8") (pinfunction "K3_8") (pintype "bidirectional"))
    )
    (net (code "122") (name "8D3") (class "Default")
      (node (ref "IC108") (pin "7") (pinfunction "DIG3_7") (pintype "output"))
      (node (ref "LED108") (pin "12") (pinfunction "K4_12") (pintype "bidirectional"))
    )
    (net (code "123") (name "8D4") (class "Default")
      (node (ref "IC108") (pin "3") (pinfunction "DIG4_3") (pintype "output"))
      (node (ref "LED108") (pin "1") (pinfunction "K5_1") (pintype "bidirectional"))
    )
    (net (code "124") (name "8D5") (class "Default")
      (node (ref "IC108") (pin "10") (pinfunction "DIG5_10") (pintype "output"))
      (node (ref "LED108") (pin "7") (pinfunction "K6_7") (pintype "bidirectional"))
    )
    (net (code "125") (name "8D6") (class "Default")
      (node (ref "IC108") (pin "5") (pinfunction "DIG6_5") (pintype "output"))
      (node (ref "LED108") (pin "2") (pinfunction "K7_2") (pintype "bidirectional"))
    )
    (net (code "126") (name "8D7") (class "Default")
      (node (ref "IC108") (pin "8") (pinfunction "DIG7_8") (pintype "output"))
      (node (ref "LED108") (pin "5") (pinfunction "K8_5") (pintype "bidirectional"))
    )
    (net (code "127") (name "8DP") (class "Default")
      (node (ref "IC108") (pin "22") (pinfunction "SEGDP_22") (pintype "output"))
      (node (ref "LED108") (pin "16") (pinfunction "A8_16") (pintype "bidirectional"))
    )
    (net (code "128") (name "8E") (class "Default")
      (node (ref "IC108") (pin "21") (pinfunction "SEGE_21") (pintype "output"))
      (node (ref "LED108") (pin "6") (pinfunction "A5_6") (pintype "bidirectional"))
    )
    (net (code "129") (name "8F") (class "Default")
      (node (ref "IC108") (pin "15") (pinfunction "SEGF_15") (pintype "output"))
      (node (ref "LED108") (pin "11") (pinfunction "A6_11") (pintype "bidirectional"))
    )
    (net (code "130") (name "8G") (class "Default")
      (node (ref "IC108") (pin "17") (pinfunction "SEGG_17") (pintype "output"))
      (node (ref "LED108") (pin "15") (pinfunction "A7_15") (pintype "bidirectional"))
    )
    (net (code "131") (name "9A") (class "Default")
      (node (ref "IC201") (pin "14") (pinfunction "SEGA_14") (pintype "output"))
      (node (ref "LED201") (pin "6") (pinfunction "6_6") (pintype "bidirectional"))
    )
    (net (code "132") (name "9B") (class "Default")
      (node (ref "IC201") (pin "16") (pinfunction "SEGB_16") (pintype "output"))
      (node (ref "LED201") (pin "14") (pinfunction "14_14") (pintype "bidirectional"))
    )
    (net (code "133") (name "9C") (class "Default")
      (node (ref "IC201") (pin "20") (pinfunction "SEGC_20") (pintype "output"))
      (node (ref "LED201") (pin "2") (pinfunction "2_2") (pintype "bidirectional"))
    )
    (net (code "134") (name "9D") (class "Default")
      (node (ref "IC201") (pin "23") (pinfunction "SEGD_23") (pintype "output"))
      (node (ref "LED201") (pin "10") (pinfunction "10_10") (pintype "bidirectional"))
    )
    (net (code "135") (name "9D0") (class "Default")
      (node (ref "IC201") (pin "2") (pinfunction "DIG0_2") (pintype "output"))
      (node (ref "LED201") (pin "3") (pinfunction "3_3") (pintype "bidirectional"))
    )
    (net (code "136") (name "9D1") (class "Default")
      (node (ref "IC201") (pin "11") (pinfunction "DIG1_11") (pintype "output"))
      (node (ref "LED201") (pin "5") (pinfunction "5_5") (pintype "bidirectional"))
    )
    (net (code "137") (name "9D2") (class "Default")
      (node (ref "IC201") (pin "6") (pinfunction "DIG2_6") (pintype "output"))
      (node (ref "LED201") (pin "7") (pinfunction "7_7") (pintype "bidirectional"))
    )
    (net (code "138") (name "9D3") (class "Default")
      (node (ref "IC201") (pin "7") (pinfunction "DIG3_7") (pintype "output"))
      (node (ref "LED201") (pin "9") (pinfunction "9_9") (pintype "bidirectional"))
    )
    (net (code "139") (name "9D4") (class "Default")
      (node (ref "IC201") (pin "3") (pinfunction "DIG4_3") (pintype "output"))
      (node (ref "LED201") (pin "11") (pinfunction "11_11") (pintype "bidirectional"))
    )
    (net (code "140") (name "9D5") (class "Default")
      (node (ref "IC201") (pin "10") (pinfunction "DIG5_10") (pintype "output"))
      (node (ref "LED201") (pin "13") (pinfunction "13_13") (pintype "bidirectional"))
    )
    (net (code "141") (name "9D6") (class "Default")
      (node (ref "IC201") (pin "5") (pinfunction "DIG6_5") (pintype "output"))
      (node (ref "LED201") (pin "15") (pinfunction "15_15") (pintype "bidirectional"))
    )
    (net (code "142") (name "9D7") (class "Default")
      (node (ref "IC201") (pin "8") (pinfunction "DIG7_8") (pintype "output"))
      (node (ref "LED201") (pin "17") (pinfunction "17_17") (pintype "bidirectional"))
    )
    (net (code "143") (name "9DP") (class "Default")
      (node (ref "IC201") (pin "22") (pinfunction "SEGDP_22") (pintype "output"))
      (node (ref "LED201") (pin "4") (pinfunction "4_4") (pintype "bidirectional"))
    )
    (net (code "144") (name "9E") (class "Default")
      (node (ref "IC201") (pin "21") (pinfunction "SEGE_21") (pintype "output"))
      (node (ref "LED201") (pin "8") (pinfunction "8_8") (pintype "bidirectional"))
    )
    (net (code "145") (name "9F") (class "Default")
      (node (ref "IC201") (pin "15") (pinfunction "SEGF_15") (pintype "output"))
      (node (ref "LED201") (pin "16") (pinfunction "16_16") (pintype "bidirectional"))
    )
    (net (code "146") (name "9G") (class "Default")
      (node (ref "IC201") (pin "17") (pinfunction "SEGG_17") (pintype "output"))
      (node (ref "LED201") (pin "12") (pinfunction "12_12") (pintype "bidirectional"))
    )
    (net (code "147") (name "ADC") (class "Default")
      (node (ref "IC301") (pin "ADC") (pinfunction "ADC_ADC") (pintype "bidirectional"))
      (node (ref "R301") (pin "2") (pinfunction "P$2_2") (pintype "bidirectional"))
      (node (ref "R302") (pin "2") (pinfunction "2_2") (pintype "passive"))
      (node (ref "R303") (pin "1") (pinfunction "1_1") (pintype "passive"))
    )
    (net (code "148") (name "BUZ") (class "Default")
      (node (ref "C308") (pin "1") (pinfunction "1_1") (pintype "passive"))
      (node (ref "IC306") (pin "18") (pinfunction "B1_18") (pintype "bidirectional"))
    )
    (net (code "149") (name "CLK") (class "Default")
      (node (ref "IC101") (pin "13") (pinfunction "CLK_13") (pintype "input"))
      (node (ref "IC102") (pin "13") (pinfunction "CLK_13") (pintype "input"))
      (node (ref "IC103") (pin "13") (pinfunction "CLK_13") (pintype "input"))
      (node (ref "IC104") (pin "13") (pinfunction "CLK_13") (pintype "input"))
      (node (ref "IC105") (pin "13") (pinfunction "CLK_13") (pintype "input"))
      (node (ref "IC106") (pin "13") (pinfunction "CLK_13") (pintype "input"))
      (node (ref "IC107") (pin "13") (pinfunction "CLK_13") (pintype "input"))
      (node (ref "IC108") (pin "13") (pinfunction "CLK_13") (pintype "input"))
      (node (ref "IC201") (pin "13") (pinfunction "CLK_13") (pintype "input"))
      (node (ref "IC306") (pin "14") (pinfunction "B5_14") (pintype "bidirectional"))
      (node (ref "J101") (pin "2") (pinfunction "S_2") (pintype "passive"))
      (node (ref "J102") (pin "2") (pinfunction "S_2") (pintype "passive"))
      (node (ref "J201") (pin "2") (pinfunction "S_2") (pintype "passive"))
      (node (ref "X301") (pin "3") (pinfunction "S_3") (pintype "passive"))
    )
    (net (code "150") (name "DIN") (class "Default")
      (node (ref "IC101") (pin "1") (pinfunction "DIN_1") (pintype "input"))
      (node (ref "IC201") (pin "1") (pinfunction "DIN_1") (pintype "input"))
      (node (ref "IC306") (pin "13") (pinfunction "B6_13") (pintype "bidirectional"))
      (node (ref "J101") (pin "3") (pinfunction "S_3") (pintype "passive"))
      (node (ref "J201") (pin "3") (pinfunction "S_3") (pintype "passive"))
      (node (ref "X301") (pin "4") (pinfunction "S_4") (pintype "passive"))
    )
    (net (code "151") (name "DOUT1") (class "Default")
      (node (ref "IC101") (pin "24") (pinfunction "DOUT_24") (pintype "output"))
      (node (ref "IC103") (pin "1") (pinfunction "DIN_1") (pintype "input"))
    )
    (net (code "152") (name "DOUT2") (class "Default")
      (node (ref "IC103") (pin "24") (pinfunction "DOUT_24") (pintype "output"))
      (node (ref "IC105") (pin "1") (pinfunction "DIN_1") (pintype "input"))
    )
    (net (code "153") (name "DOUT3") (class "Default")
      (node (ref "IC105") (pin "24") (pinfunction "DOUT_24") (pintype "output"))
      (node (ref "IC107") (pin "1") (pinfunction "DIN_1") (pintype "input"))
    )
    (net (code "154") (name "DOUT4") (class "Default")
      (node (ref "IC102") (pin "1") (pinfunction "DIN_1") (pintype "input"))
      (node (ref "IC107") (pin "24") (pinfunction "DOUT_24") (pintype "output"))
    )
    (net (code "155") (name "DOUT5") (class "Default")
      (node (ref "IC102") (pin "24") (pinfunction "DOUT_24") (pintype "output"))
      (node (ref "IC104") (pin "1") (pinfunction "DIN_1") (pintype "input"))
    )
    (net (code "156") (name "DOUT6") (class "Default")
      (node (ref "IC104") (pin "24") (pinfunction "DOUT_24") (pintype "output"))
      (node (ref "IC106") (pin "1") (pinfunction "DIN_1") (pintype "input"))
    )
    (net (code "157") (name "DOUT7") (class "Default")
      (node (ref "IC106") (pin "24") (pinfunction "DOUT_24") (pintype "output"))
      (node (ref "IC108") (pin "1") (pinfunction "DIN_1") (pintype "input"))
    )
    (net (code "158") (name "DOUT8") (class "Default")
      (node (ref "IC108") (pin "24") (pinfunction "DOUT_24") (pintype "output"))
      (node (ref "J102") (pin "3") (pinfunction "S_3") (pintype "passive"))
    )
    (net (code "159") (name "DOUT9") (class "Default")
      (node (ref "IC201") (pin "24") (pinfunction "DOUT_24") (pintype "output"))
    )
    (net (code "160") (name "DTR") (class "Default")
      (node (ref "IC401") (pin "28") (pinfunction "DTR_28") (pintype "bidirectional"))
      (node (ref "Q401") (pin "2") (pinfunction "S_2") (pintype "bidirectional"))
      (node (ref "R405") (pin "1") (pinfunction "1_1") (pintype "passive"))
    )
    (net (code "161") (name "EN") (class "Default")
      (node (ref "C301") (pin "2") (pinfunction "2_2") (pintype "passive"))
      (node (ref "C403") (pin "2") (pinfunction "2_2") (pintype "passive"))
      (node (ref "IC301") (pin "RESET") (pinfunction "RESET_RESET") (pintype "bidirectional"))
      (node (ref "J301") (pin "1") (pinfunction "1_1") (pintype "passive"))
      (node (ref "J402") (pin "1") (pinfunction "1_1") (pintype "passive"))
      (node (ref "J403") (pin "1") (pinfunction "1_1") (pintype "passive"))
      (node (ref "Q402") (pin "3") (pinfunction "D_3") (pintype "bidirectional"))
      (node (ref "R305") (pin "2") (pinfunction "2_2") (pintype "passive"))
      (node (ref "R403") (pin "2") (pinfunction "2_2") (pintype "passive"))
      (node (ref "SW301") (pin "B") (pinfunction "B_B") (pintype "passive"))
      (node (ref "SW401") (pin "A") (pinfunction "A_A") (pintype "passive"))
    )
    (net (code "162") (name "GND") (class "Default")
      (node (ref "B301") (pin "-") (pinfunction "-_-") (pintype "passive"))
      (node (ref "C101") (pin "C") (pinfunction "-_C") (pintype "passive"))
      (node (ref "C102") (pin "C") (pinfunction "-_C") (pintype "passive"))
      (node (ref "C103") (pin "2") (pinfunction "2_2") (pintype "passive"))
      (node (ref "C104") (pin "2") (pinfunction "2_2") (pintype "passive"))
      (node (ref "C105") (pin "C") (pinfunction "-_C") (pintype "passive"))
      (node (ref "C106") (pin "C") (pinfunction "-_C") (pintype "passive"))
      (node (ref "C107") (pin "2") (pinfunction "2_2") (pintype "passive"))
      (node (ref "C108") (pin "2") (pinfunction "2_2") (pintype "passive"))
      (node (ref "C109") (pin "C") (pinfunction "-_C") (pintype "passive"))
      (node (ref "C110") (pin "C") (pinfunction "-_C") (pintype "passive"))
      (node (ref "C111") (pin "2") (pinfunction "2_2") (pintype "passive"))
      (node (ref "C112") (pin "2") (pinfunction "2_2") (pintype "passive"))
      (node (ref "C113") (pin "C") (pinfunction "-_C") (pintype "passive"))
      (node (ref "C114") (pin "C") (pinfunction "-_C") (pintype "passive"))
      (node (ref "C115") (pin "2") (pinfunction "2_2") (pintype "passive"))
      (node (ref "C116") (pin "2") (pinfunction "2_2") (pintype "passive"))
      (node (ref "C201") (pin "C") (pinfunction "-_C") (pintype "passive"))
      (node (ref "C202") (pin "2") (pinfunction "2_2") (pintype "passive"))
      (node (ref "C301") (pin "1") (pinfunction "1_1") (pintype "passive"))
      (node (ref "C302") (pin "2") (pinfunction "2_2") (pintype "passive"))
      (node (ref "C303") (pin "2") (pinfunction "2_2") (pintype "passive"))
      (node (ref "C304") (pin "1") (pinfunction "1_1") (pintype "passive"))
      (node (ref "C305") (pin "2") (pinfunction "2_2") (pintype "passive"))
      (node (ref "C306") (pin "2") (pinfunction "2_2") (pintype "passive"))
      (node (ref "C307") (pin "1") (pinfunction "1_1") (pintype "passive"))
      (node (ref "C309") (pin "2") (pinfunction "2_2") (pintype "passive"))
      (node (ref "C310") (pin "1") (pinfunction "1_1") (pintype "passive"))
      (node (ref "C311") (pin "1") (pinfunction "1_1") (pintype "passive"))
      (node (ref "C401") (pin "1") (pinfunction "1_1") (pintype "passive"))
      (node (ref "C402") (pin "1") (pinfunction "1_1") (pintype "passive"))
      (node (ref "C403") (pin "1") (pinfunction "1_1") (pintype "passive"))
      (node (ref "C404") (pin "2") (pinfunction "2_2") (pintype "passive"))
      (node (ref "C405") (pin "2") (pinfunction "2_2") (pintype "passive"))
      (node (ref "C406") (pin "2") (pinfunction "2_2") (pintype "passive"))
      (node (ref "C407") (pin "2") (pinfunction "2_2") (pintype "passive"))
      (node (ref "HA301") (pin "C") (pinfunction "C_C") (pintype "passive"))
      (node (ref "IC101") (pin "4") (pinfunction "GND_4") (pintype "power_in"))
      (node (ref "IC101") (pin "9") (pinfunction "GND_9") (pintype "power_in"))
      (node (ref "IC102") (pin "4") (pinfunction "GND_4") (pintype "power_in"))
      (node (ref "IC102") (pin "9") (pinfunction "GND_9") (pintype "power_in"))
      (node (ref "IC103") (pin "4") (pinfunction "GND_4") (pintype "power_in"))
      (node (ref "IC103") (pin "9") (pinfunction "GND_9") (pintype "power_in"))
      (node (ref "IC104") (pin "4") (pinfunction "GND_4") (pintype "power_in"))
      (node (ref "IC104") (pin "9") (pinfunction "GND_9") (pintype "power_in"))
      (node (ref "IC105") (pin "4") (pinfunction "GND_4") (pintype "power_in"))
      (node (ref "IC105") (pin "9") (pinfunction "GND_9") (pintype "power_in"))
      (node (ref "IC106") (pin "4") (pinfunction "GND_4") (pintype "power_in"))
      (node (ref "IC106") (pin "9") (pinfunction "GND_9") (pintype "power_in"))
      (node (ref "IC107") (pin "4") (pinfunction "GND_4") (pintype "power_in"))
      (node (ref "IC107") (pin "9") (pinfunction "GND_9") (pintype "power_in"))
      (node (ref "IC108") (pin "4") (pinfunction "GND_4") (pintype "power_in"))
      (node (ref "IC108") (pin "9") (pinfunction "GND_9") (pintype "power_in"))
      (node (ref "IC201") (pin "4") (pinfunction "GND_4") (pintype "power_in"))
      (node (ref "IC201") (pin "9") (pinfunction "GND_9") (pintype "power_in"))
      (node (ref "IC301") (pin "GND") (pinfunction "GND_GND") (pintype "bidirectional"))
      (node (ref "IC302") (pin "10") (pinfunction "GND_10") (pintype "bidirectional"))
      (node (ref "IC302") (pin "11") (pinfunction "GND_11") (pintype "bidirectional"))
      (node (ref "IC302") (pin "12") (pinfunction "GND_12") (pintype "bidirectional"))
      (node (ref "IC302") (pin "13") (pinfunction "GND_13") (pintype "bidirectional"))
      (node (ref "IC302") (pin "5") (pinfunction "GND_5") (pintype "bidirectional"))
      (node (ref "IC302") (pin "6") (pinfunction "GND_6") (pintype "bidirectional"))
      (node (ref "IC302") (pin "7") (pinfunction "GND_7") (pintype "bidirectional"))
      (node (ref "IC302") (pin "8") (pinfunction "GND_8") (pintype "bidirectional"))
      (node (ref "IC302") (pin "9") (pinfunction "GND_9") (pintype "bidirectional"))
      (node (ref "IC303") (pin "1") (pinfunction "GND_1") (pintype "input"))
      (node (ref "IC304") (pin "2") (pinfunction "ADDR_2") (pintype "input"))
      (node (ref "IC304") (pin "3") (pinfunction "GND_3") (pintype "power_in"))
      (node (ref "IC305") (pin "1") (pinfunction "GND_1") (pintype "bidirectional"))
      (node (ref "IC305") (pin "7") (pinfunction "GND_7") (pintype "bidirectional"))
      (node (ref "IC306") (pin "10") (pinfunction "GND_10") (pintype "power_in"))
      (node (ref "IC306") (pin "19") (pinfunction "G_19") (pintype "input"))
      (node (ref "IC401") (pin "29") (pinfunction "GND_29") (pintype "bidirectional"))
      (node (ref "IC401") (pin "3") (pinfunction "GND_3") (pintype "bidirectional"))
      (node (ref "IC401") (pin "HG1") (pinfunction "GND_HG1") (pintype "bidirectional"))
      (node (ref "IC401") (pin "HG2") (pinfunction "GND_HG2") (pintype "bidirectional"))
      (node (ref "IC401") (pin "HG3") (pinfunction "GND_HG3") (pintype "bidirectional"))
      (node (ref "IC401") (pin "HG4") (pinfunction "GND_HG4") (pintype "bidirectional"))
      (node (ref "IC401") (pin "HG5") (pinfunction "GND_HG5") (pintype "bidirectional"))
      (node (ref "IC402") (pin "1") (pinfunction "GND_1") (pintype "input"))
      (node (ref "J101") (pin "5") (pinfunction "S_5") (pintype "passive"))
      (node (ref "J102") (pin "5") (pinfunction "S_5") (pintype "passive"))
      (node (ref "J201") (pin "5") (pinfunction "S_5") (pintype "passive"))
      (node (ref "J301") (pin "4") (pinfunction "4_4") (pintype "passive"))
      (node (ref "J302") (pin "1") (pinfunction "1_1") (pintype "passive"))
      (node (ref "J303") (pin "4") (pinfunction "4_4") (pintype "bidirectional"))
      (node (ref "J304") (pin "4") (pinfunction "4_4") (pintype "bidirectional"))
      (node (ref "J401") (pin "GND") (pinfunction "GND_GND") (pintype "power_in"))
      (node (ref "J401") (pin "SH@1") (pinfunction "SHIELD_SH@1") (pintype "bidirectional"))
      (node (ref "J401") (pin "SH@2") (pinfunction "SHIELD_SH@2") (pintype "bidirectional"))
      (node (ref "J401") (pin "SH@3") (pinfunction "SHIELD_SH@3") (pintype "bidirectional"))
      (node (ref "J401") (pin "SH@4") (pinfunction "SHIELD_SH@4") (pintype "bidirectional"))
      (node (ref "J401") (pin "SH@5") (pinfunction "SHIELD_SH@5") (pintype "bidirectional"))
      (node (ref "J401") (pin "SH@6") (pinfunction "SHIELD_SH@6") (pintype "bidirectional"))
      (node (ref "J402") (pin "4") (pinfunction "4_4") (pintype "passive"))
      (node (ref "J403") (pin "4") (pinfunction "4_4") (pintype "passive"))
      (node (ref "R101") (pin "1") (pinfunction "1_1") (pintype "passive"))
      (node (ref "R102") (pin "1") (pinfunction "1_1") (pintype "passive"))
      (node (ref "R105") (pin "1") (pinfunction "1_1") (pintype "passive"))
      (node (ref "R106") (pin "1") (pinfunction "1_1") (pintype "passive"))
      (node (ref "R109") (pin "1") (pinfunction "1_1") (pintype "passive"))
      (node (ref "R110") (pin "1") (pinfunction "1_1") (pintype "passive"))
      (node (ref "R113") (pin "1") (pinfunction "1_1") (pintype "passive"))
      (node (ref "R114") (pin "1") (pinfunction "1_1") (pintype "passive"))
      (node (ref "R201") (pin "1") (pinfunction "1_1") (pintype "passive"))
      (node (ref "R301") (pin "1") (pinfunction "P$1_1") (pintype "bidirectional"))
      (node (ref "R302") (pin "1") (pinfunction "1_1") (pintype "passive"))
      (node (ref "R308") (pin "1") (pinfunction "1_1") (pintype "passive"))
      (node (ref "R402") (pin "2") (pinfunction "2_2") (pintype "passive"))
      (node (ref "S301") (pin "3") (pinfunction "1_3") (pintype "passive"))
      (node (ref "S301") (pin "4") (pinfunction "1_4") (pintype "passive"))
      (node (ref "S301") (pin "C") (pinfunction "C_C") (pintype "passive"))
      (node (ref "SW301") (pin "A") (pinfunction "A_A") (pintype "passive"))
      (node (ref "SW301") (pin "SH0") (pinfunction "SH_SH0") (pintype "power_in"))
      (node (ref "SW401") (pin "B") (pinfunction "B_B") (pintype "passive"))
      (node (ref "SW401") (pin "SH0") (pinfunction "SH_SH0") (pintype "power_in"))
      (node (ref "SW402") (pin "B") (pinfunction "B_B") (pintype "passive"))
      (node (ref "SW402") (pin "SH0") (pinfunction "SH_SH0") (pintype "power_in"))
      (node (ref "U301") (pin "GND") (pinfunction "GND_GND") (pintype "power_in"))
      (node (ref "X301") (pin "6") (pinfunction "S_6") (pintype "passive"))
    )
    (net (code "163") (name "GPIO0") (class "Default")
      (node (ref "IC301") (pin "GPIO0") (pinfunction "GPIO0_GPIO0") (pintype "bidirectional"))
      (node (ref "J301") (pin "6") (pinfunction "6_6") (pintype "passive"))
      (node (ref "J402") (pin "6") (pinfunction "6_6") (pintype "passive"))
      (node (ref "J403") (pin "6") (pinfunction "6_6") (pintype "passive"))
      (node (ref "Q401") (pin "3") (pinfunction "D_3") (pintype "bidirectional"))
      (node (ref "R309") (pin "1") (pinfunction "1_1") (pintype "passive"))
      (node (ref "R406") (pin "1") (pinfunction "1_1") (pintype "passive"))
      (node (ref "S301") (pin "1") (pinfunction "2_1") (pintype "passive"))
      (node (ref "S301") (pin "2") (pinfunction "2_2") (pintype "passive"))
      (node (ref "SW402") (pin "A") (pinfunction "A_A") (pintype "passive"))
    )
    (net (code "164") (name "GPIO2") (class "Default")
      (node (ref "IC301") (pin "GPIO2") (pinfunction "GPIO2_GPIO2") (pintype "bidirectional"))
      (node (ref "IC306") (pin "3") (pinfunction "A2_3") (pintype "bidirectional"))
      (node (ref "IC306") (pin "4") (pinfunction "A3_4") (pintype "bidirectional"))
    )
    (net (code "165") (name "GPIO12") (class "Default")
      (node (ref "IC301") (pin "GPIO12") (pinfunction "GPIO12_GPIO12") (pintype "bidirectional"))
      (node (ref "IC302") (pin "3") (pinfunction "INT_3") (pintype "bidirectional"))
      (node (ref "R307") (pin "1") (pinfunction "1_1") (pintype "passive"))
    )
    (net (code "166") (name "GPIO13") (class "Default")
      (node (ref "IC301") (pin "GPIO13") (pinfunction "GPIO13_GPIO13") (pintype "bidirectional"))
      (node (ref "IC306") (pin "7") (pinfunction "A6_7") (pintype "bidirectional"))
    )
    (net (code "167") (name "GPIO14") (class "Default")
      (node (ref "IC301") (pin "GPIO14") (pinfunction "GPIO14_GPIO14") (pintype "bidirectional"))
      (node (ref "IC306") (pin "6") (pinfunction "A5_6") (pintype "bidirectional"))
    )
    (net (code "168") (name "GPIO15") (class "Default")
      (node (ref "IC301") (pin "GPIO15") (pinfunction "GPIO15_GPIO15") (pintype "bidirectional"))
      (node (ref "IC306") (pin "2") (pinfunction "A1_2") (pintype "bidirectional"))
      (node (ref "R308") (pin "2") (pinfunction "2_2") (pintype "passive"))
    )
    (net (code "169") (name "GPIO16") (class "Default")
      (node (ref "IC301") (pin "GPIO16") (pinfunction "GPIO16_GPIO16") (pintype "bidirectional"))
      (node (ref "IC306") (pin "5") (pinfunction "A4_5") (pintype "bidirectional"))
    )
    (net (code "170") (name "LED") (class "Default")
      (node (ref "IC306") (pin "17") (pinfunction "B2_17") (pintype "bidirectional"))
      (node (ref "R313") (pin "1") (pinfunction "1_1") (pintype "passive"))
    )
    (net (code "171") (name "LOAD") (class "Default")
      (node (ref "IC101") (pin "12") (pinfunction "LOAD_12") (pintype "input"))
      (node (ref "IC102") (pin "12") (pinfunction "LOAD_12") (pintype "input"))
      (node (ref "IC103") (pin "12") (pinfunction "LOAD_12") (pintype "input"))
      (node (ref "IC104") (pin "12") (pinfunction "LOAD_12") (pintype "input"))
      (node (ref "IC105") (pin "12") (pinfunction "LOAD_12") (pintype "input"))
      (node (ref "IC106") (pin "12") (pinfunction "LOAD_12") (pintype "input"))
      (node (ref "IC107") (pin "12") (pinfunction "LOAD_12") (pintype "input"))
      (node (ref "IC108") (pin "12") (pinfunction "LOAD_12") (pintype "input"))
      (node (ref "IC201") (pin "12") (pinfunction "LOAD_12") (pintype "input"))
      (node (ref "IC306") (pin "15") (pinfunction "B4_15") (pintype "bidirectional"))
      (node (ref "J101") (pin "1") (pinfunction "S_1") (pintype "passive"))
      (node (ref "J102") (pin "1") (pinfunction "S_1") (pintype "passive"))
      (node (ref "J201") (pin "1") (pinfunction "S_1") (pintype "passive"))
      (node (ref "R101") (pin "2") (pinfunction "2_2") (pintype "passive"))
      (node (ref "R102") (pin "2") (pinfunction "2_2") (pintype "passive"))
      (node (ref "R105") (pin "2") (pinfunction "2_2") (pintype "passive"))
      (node (ref "R106") (pin "2") (pinfunction "2_2") (pintype "passive"))
      (node (ref "R109") (pin "2") (pinfunction "2_2") (pintype "passive"))
      (node (ref "R110") (pin "2") (pinfunction "2_2") (pintype "passive"))
      (node (ref "R113") (pin "2") (pinfunction "2_2") (pintype "passive"))
      (node (ref "R114") (pin "2") (pinfunction "2_2") (pintype "passive"))
      (node (ref "R201") (pin "2") (pinfunction "2_2") (pintype "passive"))
      (node (ref "X301") (pin "2") (pinfunction "S_2") (pintype "passive"))
    )
    (net (code "172") (name "Net-(B301-Pad+)") (class "Default")
      (node (ref "B301") (pin "+") (pinfunction "+_+") (pintype "passive"))
      (node (ref "D303") (pin "A") (pinfunction "A_A") (pintype "passive"))
    )
    (net (code "173") (name "Net-(C308-Pad2)") (class "Default")
      (node (ref "C308") (pin "2") (pinfunction "2_2") (pintype "passive"))
      (node (ref "HA301") (pin "A") (pinfunction "A_A") (pintype "passive"))
    )
    (net (code "174") (name "Net-(D301-PadA)") (class "Default")
      (node (ref "D301") (pin "A") (pinfunction "A_A") (pintype "passive"))
      (node (ref "J301") (pin "2") (pinfunction "2_2") (pintype "passive"))
    )
    (net (code "175") (name "Net-(IC101-ISET)") (class "Default")
      (node (ref "IC101") (pin "18") (pinfunction "ISET_18") (pintype "input"))
      (node (ref "R103") (pin "2") (pinfunction "2_2") (pintype "passive"))
    )
    (net (code "176") (name "Net-(IC102-ISET)") (class "Default")
      (node (ref "IC102") (pin "18") (pinfunction "ISET_18") (pintype "input"))
      (node (ref "R104") (pin "2") (pinfunction "2_2") (pintype "passive"))
    )
    (net (code "177") (name "Net-(IC103-ISET)") (class "Default")
      (node (ref "IC103") (pin "18") (pinfunction "ISET_18") (pintype "input"))
      (node (ref "R107") (pin "2") (pinfunction "2_2") (pintype "passive"))
    )
    (net (code "178") (name "Net-(IC104-ISET)") (class "Default")
      (node (ref "IC104") (pin "18") (pinfunction "ISET_18") (pintype "input"))
      (node (ref "R108") (pin "2") (pinfunction "2_2") (pintype "passive"))
    )
    (net (code "179") (name "Net-(IC105-ISET)") (class "Default")
      (node (ref "IC105") (pin "18") (pinfunction "ISET_18") (pintype "input"))
      (node (ref "R111") (pin "2") (pinfunction "2_2") (pintype "passive"))
    )
    (net (code "180") (name "Net-(IC106-ISET)") (class "Default")
      (node (ref "IC106") (pin "18") (pinfunction "ISET_18") (pintype "input"))
      (node (ref "R112") (pin "2") (pinfunction "2_2") (pintype "passive"))
    )
    (net (code "181") (name "Net-(IC107-ISET)") (class "Default")
      (node (ref "IC107") (pin "18") (pinfunction "ISET_18") (pintype "input"))
      (node (ref "R115") (pin "2") (pinfunction "2_2") (pintype "passive"))
    )
    (net (code "182") (name "Net-(IC108-ISET)") (class "Default")
      (node (ref "IC108") (pin "18") (pinfunction "ISET_18") (pintype "input"))
      (node (ref "R116") (pin "2") (pinfunction "2_2") (pintype "passive"))
    )
    (net (code "183") (name "Net-(IC201-ISET)") (class "Default")
      (node (ref "IC201") (pin "18") (pinfunction "ISET_18") (pintype "input"))
      (node (ref "R202") (pin "2") (pinfunction "2_2") (pintype "passive"))
    )
    (net (code "184") (name "Net-(IC301-PadCH_PD)") (class "Default")
      (node (ref "IC301") (pin "CH_PD") (pinfunction "CH_PD_CH_PD") (pintype "bidirectional"))
      (node (ref "R304") (pin "1") (pinfunction "1_1") (pintype "passive"))
    )
    (net (code "185") (name "Net-(IC302-32KHZ)") (class "Default")
      (node (ref "IC302") (pin "1") (pinfunction "32KHZ_1") (pintype "output"))
      (node (ref "R306") (pin "1") (pinfunction "1_1") (pintype "passive"))
    )
    (net (code "186") (name "Net-(IC302-VBAT)") (class "Default")
      (node (ref "D302") (pin "C") (pinfunction "C_C") (pintype "passive"))
      (node (ref "D303") (pin "C") (pinfunction "C_C") (pintype "passive"))
      (node (ref "IC302") (pin "14") (pinfunction "VBAT_14") (pintype "bidirectional"))
    )
    (net (code "187") (name "Net-(IC304-DVI)") (class "Default")
      (node (ref "C309") (pin "1") (pinfunction "1_1") (pintype "passive"))
      (node (ref "IC304") (pin "5") (pinfunction "DVI_5") (pintype "bidirectional"))
      (node (ref "R312") (pin "2") (pinfunction "2_2") (pintype "passive"))
    )
    (net (code "188") (name "Net-(IC401-D+)") (class "Default")
      (node (ref "IC401") (pin "4") (pinfunction "D+_4") (pintype "bidirectional"))
      (node (ref "J401") (pin "D+") (pinfunction "D+_D+") (pintype "bidirectional"))
    )
    (net (code "189") (name "Net-(IC401-D-)") (class "Default")
      (node (ref "IC401") (pin "5") (pinfunction "D-_5") (pintype "bidirectional"))
      (node (ref "J401") (pin "D-") (pinfunction "D-_D-") (pintype "bidirectional"))
    )
    (net (code "190") (name "Net-(IC401-~{RST})") (class "Default")
      (node (ref "IC401") (pin "9") (pinfunction "~{RST}_9") (pintype "bidirectional"))
      (node (ref "R401") (pin "1") (pinfunction "1_1") (pintype "passive"))
    )
    (net (code "191") (name "Net-(IC401-~{SUSPEND})") (class "Default")
      (node (ref "IC401") (pin "11") (pinfunction "~{SUSPEND}_11") (pintype "bidirectional"))
      (node (ref "R402") (pin "1") (pinfunction "1_1") (pintype "passive"))
    )
    (net (code "192") (name "Net-(Q401-G)") (class "Default")
      (node (ref "Q401") (pin "1") (pinfunction "G_1") (pintype "bidirectional"))
      (node (ref "R404") (pin "2") (pinfunction "2_2") (pintype "passive"))
    )
    (net (code "193") (name "Net-(Q402-G)") (class "Default")
      (node (ref "Q402") (pin "1") (pinfunction "G_1") (pintype "bidirectional"))
      (node (ref "R405") (pin "2") (pinfunction "2_2") (pintype "passive"))
    )
    (net (code "194") (name "Net-(R310-Pad1)") (class "Default")
      (node (ref "R310") (pin "1") (pinfunction "1_1") (pintype "passive"))
      (node (ref "R311") (pin "1") (pinfunction "1_1") (pintype "passive"))
      (node (ref "SJ301") (pin "2") (pinfunction "2_2") (pintype "passive"))
    )
    (net (code "195") (name "Net-(R313-Pad2)") (class "Default")
      (node (ref "R313") (pin "2") (pinfunction "2_2") (pintype "passive"))
      (node (ref "S301") (pin "A") (pinfunction "A_A") (pintype "passive"))
    )
    (net (code "196") (name "RTS") (class "Default")
      (node (ref "IC401") (pin "24") (pinfunction "RTS_24") (pintype "bidirectional"))
      (node (ref "Q402") (pin "2") (pinfunction "S_2") (pintype "bidirectional"))
      (node (ref "R404") (pin "1") (pinfunction "1_1") (pintype "passive"))
    )
    (net (code "197") (name "RX") (class "Default")
      (node (ref "IC301") (pin "RXD0") (pinfunction "RX_RXD0") (pintype "bidirectional"))
      (node (ref "IC401") (pin "26") (pinfunction "TXD_26") (pintype "bidirectional"))
      (node (ref "J301") (pin "5") (pinfunction "5_5") (pintype "passive"))
      (node (ref "J402") (pin "5") (pinfunction "5_5") (pintype "passive"))
      (node (ref "J403") (pin "5") (pinfunction "5_5") (pintype "passive"))
    )
    (net (code "198") (name "SCL") (class "Default")
      (node (ref "IC301") (pin "GPIO5") (pinfunction "GPIO5_GPIO5") (pintype "bidirectional"))
      (node (ref "IC302") (pin "16") (pinfunction "SCL_16") (pintype "bidirectional"))
      (node (ref "IC304") (pin "6") (pinfunction "SCL_6") (pintype "bidirectional"))
      (node (ref "IC305") (pin "4") (pinfunction "SCK/SCL_4") (pintype "bidirectional"))
      (node (ref "J303") (pin "1") (pinfunction "1_1") (pintype "bidirectional"))
      (node (ref "J304") (pin "1") (pinfunction "1_1") (pintype "bidirectional"))
      (node (ref "R311") (pin "2") (pinfunction "2_2") (pintype "passive"))
      (node (ref "U301") (pin "SCK") (pinfunction "SCK_SCK") (pintype "input"))
    )
    (net (code "199") (name "SDA") (class "Default")
      (node (ref "IC301") (pin "GPIO4") (pinfunction "GPIO4_GPIO4") (pintype "bidirectional"))
      (node (ref "IC302") (pin "15") (pinfunction "SDA_15") (pintype "bidirectional"))
      (node (ref "IC304") (pin "4") (pinfunction "SDA_4") (pintype "bidirectional"))
      (node (ref "IC305") (pin "3") (pinfunction "SDI/SDA_3") (pintype "bidirectional"))
      (node (ref "J303") (pin "2") (pinfunction "2_2") (pintype "bidirectional"))
      (node (ref "J304") (pin "2") (pinfunction "2_2") (pintype "bidirectional"))
      (node (ref "R310") (pin "2") (pinfunction "2_2") (pintype "passive"))
      (node (ref "U301") (pin "DATA") (pinfunction "DATA_DATA") (pintype "bidirectional"))
    )
    (net (code "200") (name "TX") (class "Default")
      (node (ref "IC301") (pin "TXD0") (pinfunction "TX_TXD0") (pintype "bidirectional"))
      (node (ref "IC401") (pin "25") (pinfunction "RXD_25") (pintype "bidirectional"))
      (node (ref "J301") (pin "3") (pinfunction "3_3") (pintype "passive"))
      (node (ref "J402") (pin "3") (pinfunction "3_3") (pintype "passive"))
      (node (ref "J403") (pin "3") (pinfunction "3_3") (pintype "passive"))
    )
    (net (code "201") (name "VBUS") (class "Default")
      (node (ref "C406") (pin "1") (pinfunction "1_1") (pintype "passive"))
      (node (ref "C407") (pin "1") (pinfunction "1_1") (pintype "passive"))
      (node (ref "IC401") (pin "8") (pinfunction "VBUS_8") (pintype "bidirectional"))
      (node (ref "IC402") (pin "3") (pinfunction "IN_3") (pintype "input"))
      (node (ref "J401") (pin "VBUS") (pinfunction "VBUS_VBUS") (pintype "power_in"))
    )
    (net (code "202") (name "VIN") (class "Default")
      (node (ref "C305") (pin "1") (pinfunction "1_1") (pintype "passive"))
      (node (ref "C306") (pin "1") (pinfunction "1_1") (pintype "passive"))
      (node (ref "IC303") (pin "3") (pinfunction "IN_3") (pintype "input"))
      (node (ref "J302") (pin "2") (pinfunction "2_2") (pintype "passive"))
      (node (ref "SJ302") (pin "3") (pinfunction "3_3") (pintype "passive"))
    )
    (net (code "203") (name "V_OUT") (class "Default")
      (node (ref "IC306") (pin "1") (pinfunction "DIR_1") (pintype "input"))
      (node (ref "IC306") (pin "20") (pinfunction "VCC_20") (pintype "power_in"))
      (node (ref "SJ302") (pin "1") (pinfunction "1_1") (pintype "passive"))
      (node (ref "X301") (pin "5") (pinfunction "S_5") (pintype "passive"))
    )
    (net (code "204") (name "WR") (class "Default")
      (node (ref "IC306") (pin "16") (pinfunction "B3_16") (pintype "bidirectional"))
      (node (ref "X301") (pin "1") (pinfunction "S_1") (pintype "passive"))
    )
    (net (code "205") (name "unconnected-(IC302-RST-Pad4)") (class "Default")
      (node (ref "IC302") (pin "4") (pinfunction "RST_4") (pintype "bidirectional"))
    )
    (net (code "206") (name "unconnected-(IC305-SDO{slash}ADR-Pad5)") (class "Default")
      (node (ref "IC305") (pin "5") (pinfunction "SDO/ADR_5") (pintype "bidirectional"))
    )
    (net (code "207") (name "unconnected-(IC305-~{CS}-Pad2)") (class "Default")
      (node (ref "IC305") (pin "2") (pinfunction "~{CS}_2") (pintype "bidirectional"))
    )
    (net (code "208") (name "unconnected-(IC306-A7-Pad8)") (class "Default")
      (node (ref "IC306") (pin "8") (pinfunction "A7_8") (pintype "bidirectional"))
    )
    (net (code "209") (name "unconnected-(IC306-A8-Pad9)") (class "Default")
      (node (ref "IC306") (pin "9") (pinfunction "A8_9") (pintype "bidirectional"))
    )
    (net (code "210") (name "unconnected-(IC306-B7-Pad12)") (class "Default")
      (node (ref "IC306") (pin "12") (pinfunction "B7_12") (pintype "bidirectional"))
    )
    (net (code "211") (name "unconnected-(IC306-B8-Pad11)") (class "Default")
      (node (ref "IC306") (pin "11") (pinfunction "B8_11") (pintype "bidirectional"))
    )
    (net (code "212") (name "unconnected-(IC401-CTS-Pad23)") (class "Default")
      (node (ref "IC401") (pin "23") (pinfunction "CTS_23") (pintype "bidirectional"))
    )
    (net (code "213") (name "unconnected-(IC401-DCD-Pad1)") (class "Default")
      (node (ref "IC401") (pin "1") (pinfunction "DCD_1") (pintype "bidirectional"))
    )
    (net (code "214") (name "unconnected-(IC401-DSR-Pad27)") (class "Default")
      (node (ref "IC401") (pin "27") (pinfunction "DSR_27") (pintype "bidirectional"))
    )
    (net (code "215") (name "unconnected-(IC401-NC-Pad10)") (class "Default")
      (node (ref "IC401") (pin "10") (pinfunction "NC_10") (pintype "bidirectional"))
    )
    (net (code "216") (name "unconnected-(IC401-NC-Pad13)") (class "Default")
      (node (ref "IC401") (pin "13") (pinfunction "NC_13") (pintype "bidirectional"))
    )
    (net (code "217") (name "unconnected-(IC401-NC-Pad14)") (class "Default")
      (node (ref "IC401") (pin "14") (pinfunction "NC_14") (pintype "bidirectional"))
    )
    (net (code "218") (name "unconnected-(IC401-NC-Pad15)") (class "Default")
      (node (ref "IC401") (pin "15") (pinfunction "NC_15") (pintype "bidirectional"))
    )
    (net (code "219") (name "unconnected-(IC401-NC-Pad16)") (class "Default")
      (node (ref "IC401") (pin "16") (pinfunction "NC_16") (pintype "bidirectional"))
    )
    (net (code "220") (name "unconnected-(IC401-NC-Pad17)") (class "Default")
      (node (ref "IC401") (pin "17") (pinfunction "NC_17") (pintype "bidirectional"))
    )
    (net (code "221") (name "unconnected-(IC401-NC-Pad19)") (class "Default")
      (node (ref "IC401") (pin "19") (pinfunction "NC_19") (pintype "bidirectional"))
    )
    (net (code "222") (name "unconnected-(IC401-NC-Pad20)") (class "Default")
      (node (ref "IC401") (pin "20") (pinfunction "NC_20") (pintype "bidirectional"))
    )
    (net (code "223") (name "unconnected-(IC401-NC-Pad21)") (class "Default")
      (node (ref "IC401") (pin "21") (pinfunction "NC_21") (pintype "bidirectional"))
    )
    (net (code "224") (name "unconnected-(IC401-NC-Pad22)") (class "Default")
      (node (ref "IC401") (pin "22") (pinfunction "NC_22") (pintype "bidirectional"))
    )
    (net (code "225") (name "unconnected-(IC401-NC{slash}VPP-Pad18)") (class "Default")
      (node (ref "IC401") (pin "18") (pinfunction "NC/VPP_18") (pintype "bidirectional"))
    )
    (net (code "226") (name "unconnected-(IC401-RI-Pad2)") (class "Default")
      (node (ref "IC401") (pin "2") (pinfunction "RI_2") (pintype "bidirectional"))
    )
    (net (code "227") (name "unconnected-(IC401-SUSPEND-Pad12)") (class "Default")
      (node (ref "IC401") (pin "12") (pinfunction "SUSPEND_12") (pintype "bidirectional"))
    )
    (net (code "228") (name "unconnected-(J401-PadID)") (class "Default")
      (node (ref "J401") (pin "ID") (pinfunction "ID_ID") (pintype "bidirectional"))
    )
    (net (code "229") (name "unconnected-(LED201-Pad1)") (class "Default")
      (node (ref "LED201") (pin "1") (pinfunction "1_1") (pintype "bidirectional"))
    )
  )
)
